# HitconBadge2018.net
KiCad netlist of a schematic drawn in EAGLE
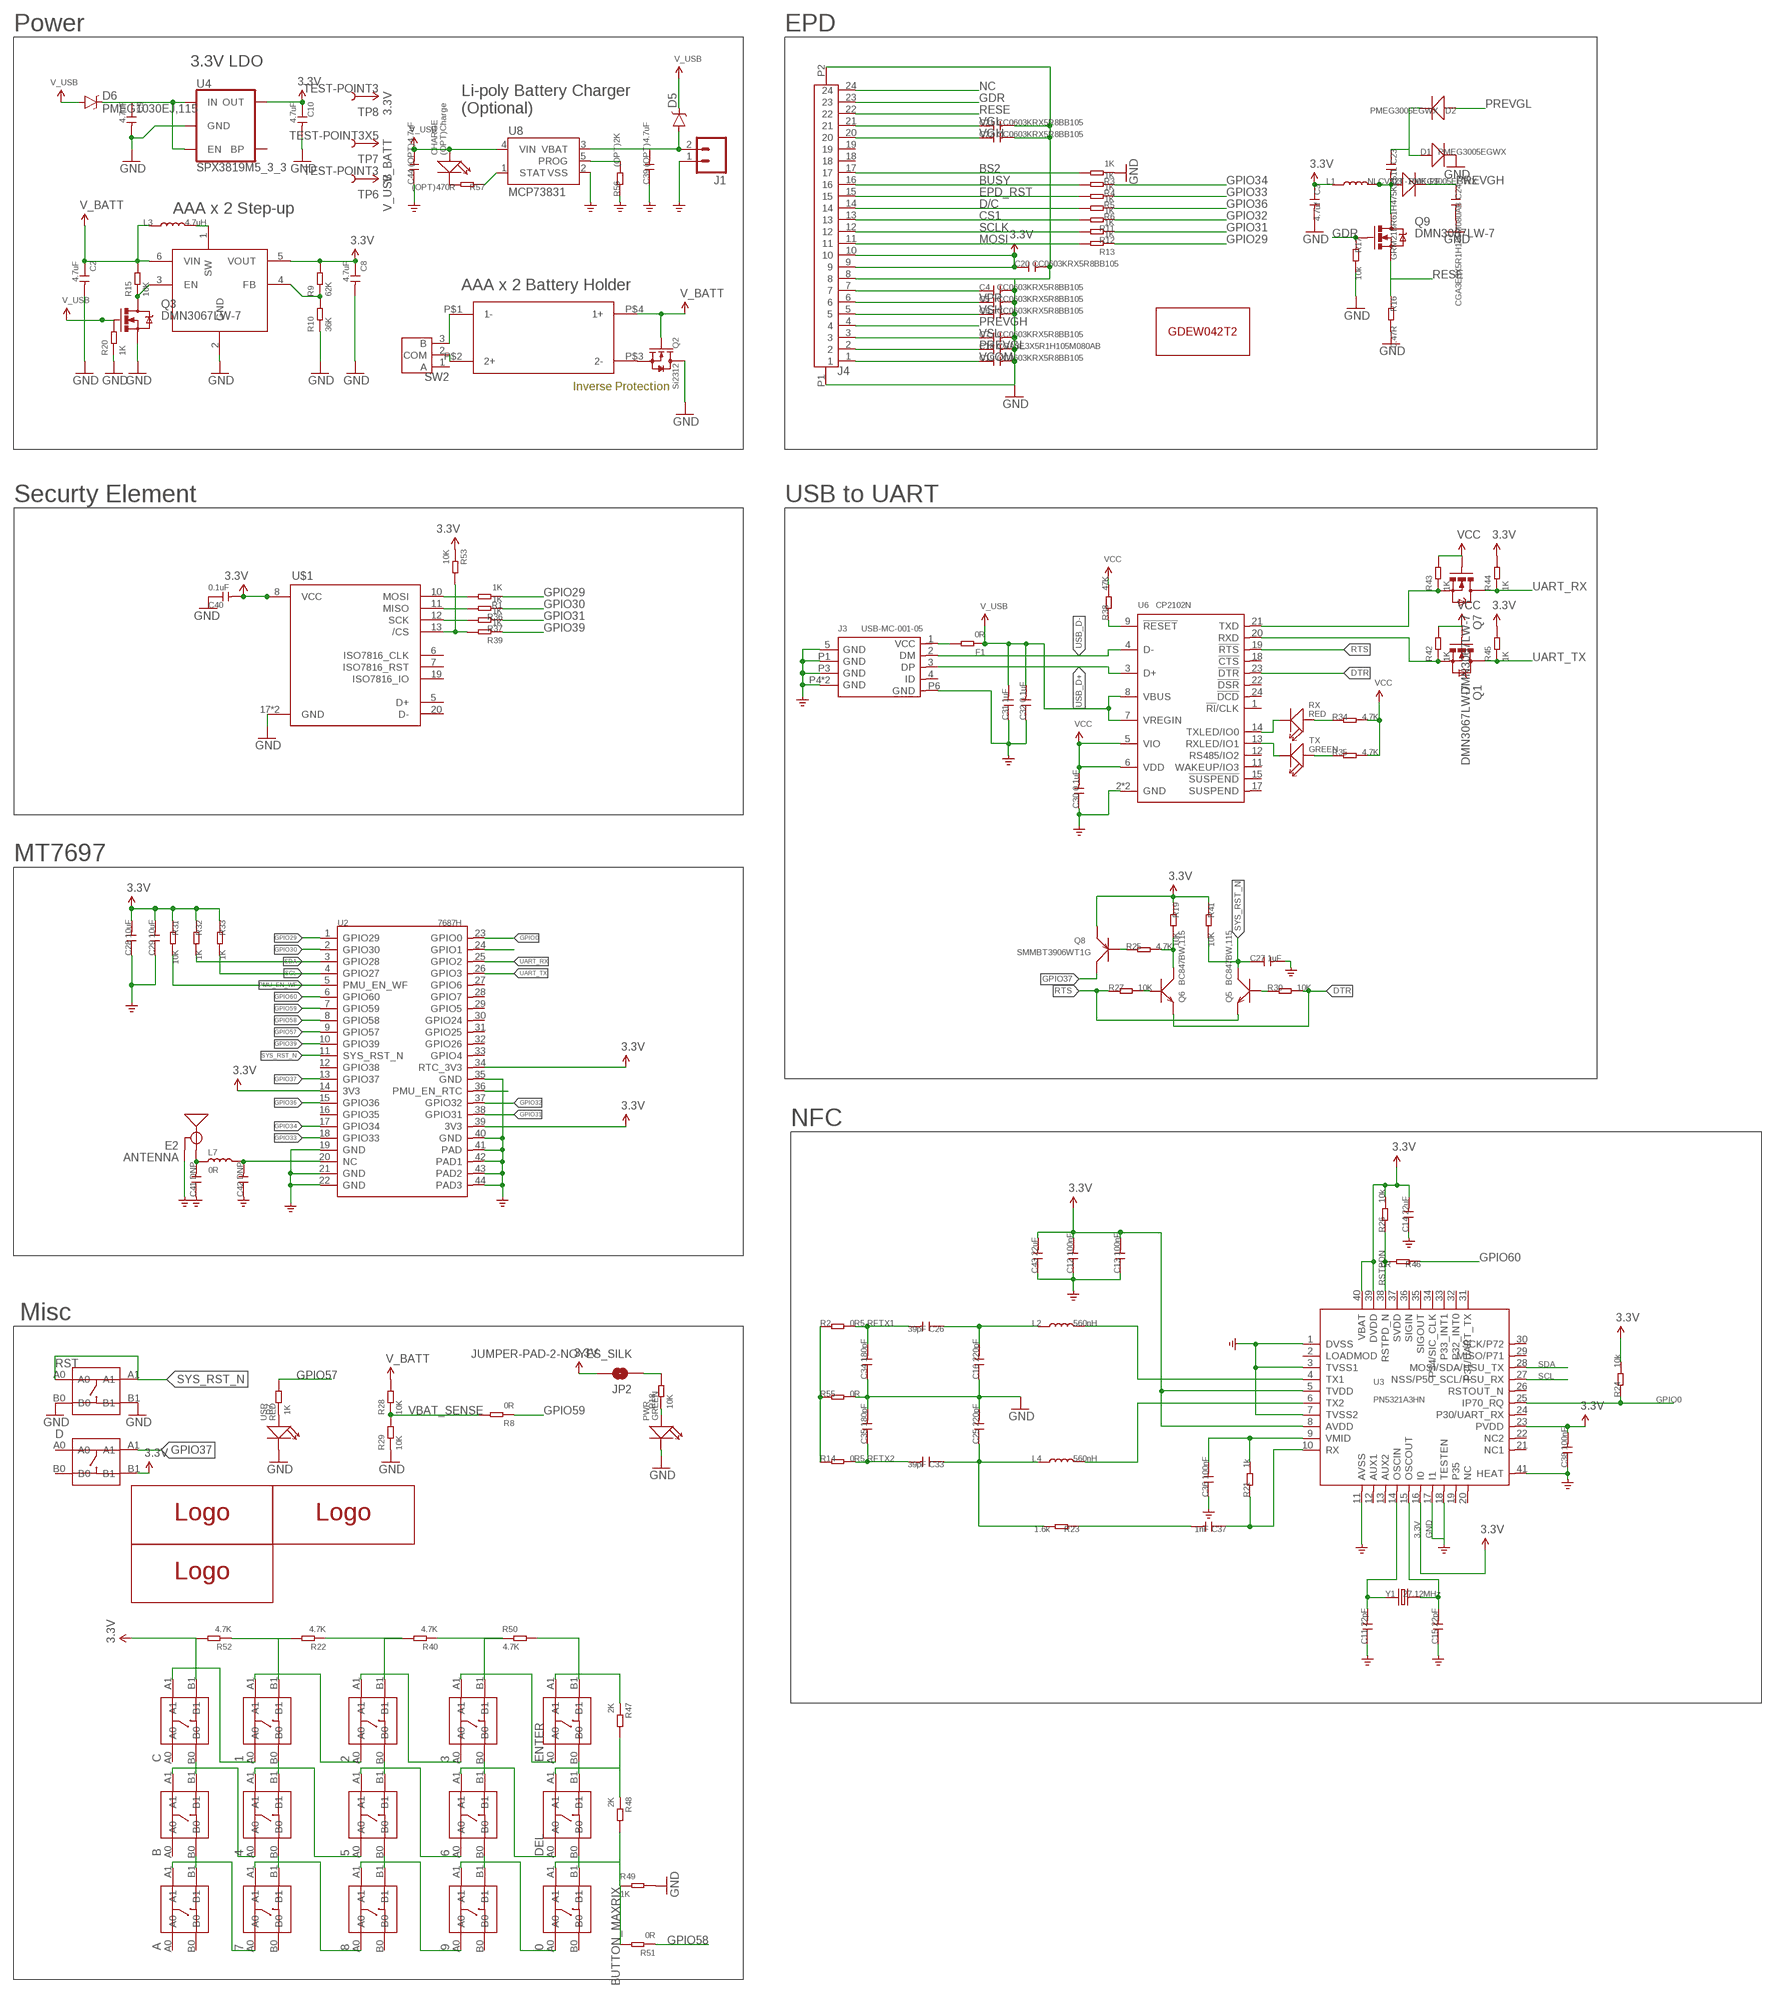
[diagram p0: schematic, sheet 1]

(export (version "E")
  (design (tool "Eeschema 10.0.6"))
  (components
    (comp (ref "0")
      (value "BUTTON-4P-3.3X3.3")
      (footprint "eagle-import:4P-SMD-3.4X3.4X1.3H")
      (libsource (lib "eagle-import") (part "BUTTON-4P-3.3X3.3"))
    )
    (comp (ref "1")
      (value "BUTTON-4P-3.3X3.3")
      (footprint "eagle-import:4P-SMD-3.4X3.4X1.3H")
      (libsource (lib "eagle-import") (part "BUTTON-4P-3.3X3.3"))
    )
    (comp (ref "2")
      (value "BUTTON-4P-3.3X3.3")
      (footprint "eagle-import:4P-SMD-3.4X3.4X1.3H")
      (libsource (lib "eagle-import") (part "BUTTON-4P-3.3X3.3"))
    )
    (comp (ref "3")
      (value "BUTTON-4P-3.3X3.3")
      (footprint "eagle-import:4P-SMD-3.4X3.4X1.3H")
      (libsource (lib "eagle-import") (part "BUTTON-4P-3.3X3.3"))
    )
    (comp (ref "4")
      (value "BUTTON-4P-3.3X3.3")
      (footprint "eagle-import:4P-SMD-3.4X3.4X1.3H")
      (libsource (lib "eagle-import") (part "BUTTON-4P-3.3X3.3"))
    )
    (comp (ref "5")
      (value "BUTTON-4P-3.3X3.3")
      (footprint "eagle-import:4P-SMD-3.4X3.4X1.3H")
      (libsource (lib "eagle-import") (part "BUTTON-4P-3.3X3.3"))
    )
    (comp (ref "6")
      (value "BUTTON-4P-3.3X3.3")
      (footprint "eagle-import:4P-SMD-3.4X3.4X1.3H")
      (libsource (lib "eagle-import") (part "BUTTON-4P-3.3X3.3"))
    )
    (comp (ref "7")
      (value "BUTTON-4P-3.3X3.3")
      (footprint "eagle-import:4P-SMD-3.4X3.4X1.3H")
      (libsource (lib "eagle-import") (part "BUTTON-4P-3.3X3.3"))
    )
    (comp (ref "8")
      (value "BUTTON-4P-3.3X3.3")
      (footprint "eagle-import:4P-SMD-3.4X3.4X1.3H")
      (libsource (lib "eagle-import") (part "BUTTON-4P-3.3X3.3"))
    )
    (comp (ref "9")
      (value "BUTTON-4P-3.3X3.3")
      (footprint "eagle-import:4P-SMD-3.4X3.4X1.3H")
      (libsource (lib "eagle-import") (part "BUTTON-4P-3.3X3.3"))
    )
    (comp (ref "A")
      (value "BUTTON-4P-3.3X3.3")
      (footprint "eagle-import:4P-SMD-3.4X3.4X1.3H")
      (libsource (lib "eagle-import") (part "BUTTON-4P-3.3X3.3"))
    )
    (comp (ref "B")
      (value "BUTTON-4P-3.3X3.3")
      (footprint "eagle-import:4P-SMD-3.4X3.4X1.3H")
      (libsource (lib "eagle-import") (part "BUTTON-4P-3.3X3.3"))
    )
    (comp (ref "C")
      (value "BUTTON-4P-3.3X3.3")
      (footprint "eagle-import:4P-SMD-3.4X3.4X1.3H")
      (libsource (lib "eagle-import") (part "BUTTON-4P-3.3X3.3"))
    )
    (comp (ref "C2")
      (value "4.7uF")
      (footprint "eagle-import:C0603@1")
      (libsource (lib "eagle-import") (part "CAP-0603"))
    )
    (comp (ref "C3")
      (value "4.7uf")
      (footprint "eagle-import:C0603")
      (libsource (lib "eagle-import") (part "C-0603"))
    )
    (comp (ref "C4")
      (value "CC0603KRX5R8BB105")
      (footprint "eagle-import:C0603")
      (libsource (lib "eagle-import") (part "C-0603"))
    )
    (comp (ref "C5")
      (value "CC0603KRX5R8BB105")
      (footprint "eagle-import:C0603")
      (libsource (lib "eagle-import") (part "C-0603"))
    )
    (comp (ref "C6")
      (value "CC0603KRX5R8BB105")
      (footprint "eagle-import:C0603")
      (libsource (lib "eagle-import") (part "C-0603"))
    )
    (comp (ref "C7")
      (value "CC0603KRX5R8BB105")
      (footprint "eagle-import:C0603")
      (libsource (lib "eagle-import") (part "C-0603"))
    )
    (comp (ref "C8")
      (value "4.7uF")
      (footprint "eagle-import:C0603@1")
      (libsource (lib "eagle-import") (part "CAP-0603"))
    )
    (comp (ref "C9")
      (value "4.7uF")
      (footprint "eagle-import:C0603@1")
      (libsource (lib "eagle-import") (part "CAP-0603"))
    )
    (comp (ref "C10")
      (value "4.7uF")
      (footprint "eagle-import:C0603@1")
      (libsource (lib "eagle-import") (part "CAP-0603"))
    )
    (comp (ref "C11")
      (value "22pF")
      (footprint "eagle-import:C0402")
      (libsource (lib "eagle-import") (part "C-0402"))
    )
    (comp (ref "C12")
      (value "100nF")
      (footprint "eagle-import:C0402")
      (libsource (lib "eagle-import") (part "C-0402"))
    )
    (comp (ref "C13")
      (value "100nF")
      (footprint "eagle-import:C0402")
      (libsource (lib "eagle-import") (part "C-0402"))
    )
    (comp (ref "C14")
      (value "22uF")
      (footprint "eagle-import:C0603")
      (libsource (lib "eagle-import") (part "C-0603"))
    )
    (comp (ref "C15")
      (value "22pF")
      (footprint "eagle-import:C0402")
      (libsource (lib "eagle-import") (part "C-0402"))
    )
    (comp (ref "C16")
      (value "220pF")
      (footprint "eagle-import:C0402")
      (libsource (lib "eagle-import") (part "C-0402"))
    )
    (comp (ref "C18")
      (value "CGA3E3X5R1H105M080AB")
      (footprint "eagle-import:C0603")
      (libsource (lib "eagle-import") (part "C-0603"))
    )
    (comp (ref "C19")
      (value "CC0603KRX5R8BB105")
      (footprint "eagle-import:C0603")
      (libsource (lib "eagle-import") (part "C-0603"))
    )
    (comp (ref "C20")
      (value "CC0603KRX5R8BB105")
      (footprint "eagle-import:C0603")
      (libsource (lib "eagle-import") (part "C-0603"))
    )
    (comp (ref "C21")
      (value "CC0603KRX5R8BB105")
      (footprint "eagle-import:C0603")
      (libsource (lib "eagle-import") (part "C-0603"))
    )
    (comp (ref "C22")
      (value "CC0603KRX5R8BB105")
      (footprint "eagle-import:C0603")
      (libsource (lib "eagle-import") (part "C-0603"))
    )
    (comp (ref "C23")
      (value "GRM21BR61H475KE51L")
      (footprint "eagle-import:C0805")
      (libsource (lib "eagle-import") (part "C-0805"))
    )
    (comp (ref "C24")
      (value "CGA3E3X5R1H105M080AB")
      (footprint "eagle-import:C0603")
      (libsource (lib "eagle-import") (part "C-0603"))
    )
    (comp (ref "C25")
      (value "220pF")
      (footprint "eagle-import:C0402")
      (libsource (lib "eagle-import") (part "C-0402"))
    )
    (comp (ref "C26")
      (value "39pF")
      (footprint "eagle-import:C0402")
      (libsource (lib "eagle-import") (part "C-0402"))
    )
    (comp (ref "C27")
      (value "1uF")
      (footprint "eagle-import:C0402")
      (libsource (lib "eagle-import") (part "C-0402"))
    )
    (comp (ref "C28")
      (value "10uF")
      (footprint "eagle-import:C0603")
      (libsource (lib "eagle-import") (part "C-0603"))
    )
    (comp (ref "C29")
      (value "10uF")
      (footprint "eagle-import:C0603")
      (libsource (lib "eagle-import") (part "C-0603"))
    )
    (comp (ref "C30")
      (value "0.1uF")
      (footprint "eagle-import:C0402")
      (libsource (lib "eagle-import") (part "C-0402"))
    )
    (comp (ref "C31")
      (value "1uF")
      (footprint "eagle-import:C0402")
      (libsource (lib "eagle-import") (part "C-0402"))
    )
    (comp (ref "C32")
      (value "0.1uF")
      (footprint "eagle-import:C0402")
      (libsource (lib "eagle-import") (part "C-0402"))
    )
    (comp (ref "C33")
      (value "39pF")
      (footprint "eagle-import:C0402")
      (libsource (lib "eagle-import") (part "C-0402"))
    )
    (comp (ref "C34")
      (value "180pF")
      (footprint "eagle-import:C0402")
      (libsource (lib "eagle-import") (part "C-0402"))
    )
    (comp (ref "C35")
      (value "180pF")
      (footprint "eagle-import:C0402")
      (libsource (lib "eagle-import") (part "C-0402"))
    )
    (comp (ref "C36")
      (value "100nF")
      (footprint "eagle-import:C0402")
      (libsource (lib "eagle-import") (part "C-0402"))
    )
    (comp (ref "C37")
      (value "1nF")
      (footprint "eagle-import:C0402")
      (libsource (lib "eagle-import") (part "C-0402"))
    )
    (comp (ref "C38")
      (value "100nF")
      (footprint "eagle-import:C0402")
      (libsource (lib "eagle-import") (part "C-0402"))
    )
    (comp (ref "C39")
      (value "(OPT)4.7uF")
      (footprint "eagle-import:C0603")
      (libsource (lib "eagle-import") (part "C-0603"))
    )
    (comp (ref "C40")
      (value "0.1uF")
      (footprint "eagle-import:C0402@1")
      (libsource (lib "eagle-import") (part "CAP-0402"))
    )
    (comp (ref "C41")
      (value "DNP")
      (footprint "eagle-import:C0402")
      (libsource (lib "eagle-import") (part "C-0402"))
    )
    (comp (ref "C42")
      (value "DNP")
      (footprint "eagle-import:C0402")
      (libsource (lib "eagle-import") (part "C-0402"))
    )
    (comp (ref "C43")
      (value "22uF")
      (footprint "eagle-import:C0603")
      (libsource (lib "eagle-import") (part "C-0603"))
    )
    (comp (ref "C44")
      (value "(OPT)4.7uF")
      (footprint "eagle-import:C0603")
      (libsource (lib "eagle-import") (part "C-0603"))
    )
    (comp (ref "CHARGE")
      (value "(OPT)Charge")
      (footprint "eagle-import:LED-0603")
      (libsource (lib "eagle-import") (part "LED'0603'"))
    )
    (comp (ref "D")
      (value "BUTTON-4P-3.3X3.3")
      (footprint "eagle-import:4P-SMD-3.4X3.4X1.3H")
      (libsource (lib "eagle-import") (part "BUTTON-4P-3.3X3.3"))
    )
    (comp (ref "D1")
      (value "PMEG3005EGWX")
      (footprint "eagle-import:SOD123")
      (libsource (lib "eagle-import") (part "D'1206'"))
    )
    (comp (ref "D2")
      (value "PMEG3005EGWX")
      (footprint "eagle-import:SOD123")
      (libsource (lib "eagle-import") (part "D'1206'"))
    )
    (comp (ref "D3")
      (value "PMEG3005EGWX")
      (footprint "eagle-import:SOD123")
      (libsource (lib "eagle-import") (part "D'1206'"))
    )
    (comp (ref "D5")
      (value "(OPT)PMEG1030EJ,115")
      (footprint "eagle-import:SOD-323")
      (libsource (lib "eagle-import") (part "DIODE-SCHOTTKY-BAT20J"))
    )
    (comp (ref "D6")
      (value "PMEG1030EJ,115")
      (footprint "eagle-import:SOD-323")
      (libsource (lib "eagle-import") (part "DIODE-SCHOTTKY-BAT20J"))
    )
    (comp (ref "DEL")
      (value "BUTTON-4P-3.3X3.3")
      (footprint "eagle-import:4P-SMD-3.4X3.4X1.3H")
      (libsource (lib "eagle-import") (part "BUTTON-4P-3.3X3.3"))
    )
    (comp (ref "E2")
      (value "ANTENNA")
      (footprint "eagle-import:2450AT18D0100E")
      (libsource (lib "eagle-import") (part "ANTENNA"))
    )
    (comp (ref "ENTER")
      (value "BUTTON-4P-3.3X3.3")
      (footprint "eagle-import:4P-SMD-3.4X3.4X1.3H")
      (libsource (lib "eagle-import") (part "BUTTON-4P-3.3X3.3"))
    )
    (comp (ref "F1")
      (value "0R")
      (footprint "eagle-import:R0603")
      (libsource (lib "eagle-import") (part "RES-0603"))
    )
    (comp (ref "J1")
      (value "M02-JST-2MM-SMT")
      (footprint "eagle-import:JST-2-SMD")
      (libsource (lib "eagle-import") (part "M02-JST-2MM-SMT"))
    )
    (comp (ref "J3")
      (value "USB-MC-001-05")
      (footprint "eagle-import:MICRO-USB5+5P-SMD-0.65-7.2X5.06MM")
      (libsource (lib "eagle-import") (part "MICRO-USB5+4P"))
    )
    (comp (ref "J4")
      (value "FPC-CONNECTOR-24P-0.5'ST-FPC-052024-B'")
      (footprint "eagle-import:24P-0.5")
      (libsource (lib "eagle-import") (part "FPC-CONNECTOR-24P-0.5'ST-FPC-052024-B'"))
    )
    (comp (ref "JP2")
      (value "JUMPER-PAD-2-NOYES_SILK")
      (footprint "eagle-import:PAD-JUMPER-2-NO_YES_SILK")
      (libsource (lib "eagle-import") (part "JUMPER-PAD-2-NOYES_SILK"))
    )
    (comp (ref "L1")
      (value "NLCV32T-100K-PF")
      (footprint "eagle-import:1813@1")
      (libsource (lib "eagle-import") (part "L'1813'"))
    )
    (comp (ref "L2")
      (value "560nH")
      (footprint "eagle-import:L0603@1")
      (libsource (lib "eagle-import") (part "L'0603'"))
    )
    (comp (ref "L3")
      (value "4.7uH")
      (footprint "eagle-import:1616BZ@1")
      (libsource (lib "eagle-import") (part "L'1616BZ'"))
    )
    (comp (ref "L4")
      (value "560nH")
      (footprint "eagle-import:L0603@1")
      (libsource (lib "eagle-import") (part "L'0603'"))
    )
    (comp (ref "L7")
      (value "0R")
      (footprint "eagle-import:L0402")
      (libsource (lib "eagle-import") (part "INDUCTOR/FERRITE-BEAD-0402"))
    )
    (comp (ref "PWR")
      (value "GREEN")
      (footprint "eagle-import:LED-0603")
      (libsource (lib "eagle-import") (part "LED'0603'"))
    )
    (comp (ref "Q1")
      (value "DMN3067LW-7")
      (footprint "eagle-import:SOT323")
      (libsource (lib "eagle-import") (part "MOSFET-NCHANNEL2N7002PW"))
    )
    (comp (ref "Q2")
      (value "Si2312")
      (footprint "eagle-import:SOT23")
      (libsource (lib "eagle-import") (part "MOSFET-N'SOT23'"))
    )
    (comp (ref "Q3")
      (value "DMN3067LW-7")
      (footprint "eagle-import:SOT323")
      (libsource (lib "eagle-import") (part "MOSFET-NCHANNEL2N7002PW"))
    )
    (comp (ref "Q5")
      (value "BC847BW,115")
      (footprint "eagle-import:SOT-323")
      (libsource (lib "eagle-import") (part "TRANSISTOR-NPN-SOT323"))
    )
    (comp (ref "Q6")
      (value "BC847BW,115")
      (footprint "eagle-import:SOT-323")
      (libsource (lib "eagle-import") (part "TRANSISTOR-NPN-SOT323"))
    )
    (comp (ref "Q7")
      (value "DMN3067LW-7")
      (footprint "eagle-import:SOT323")
      (libsource (lib "eagle-import") (part "MOSFET-NCHANNEL2N7002PW"))
    )
    (comp (ref "Q8")
      (value "SMMBT3906WT1G")
      (footprint "eagle-import:SOT-323")
      (libsource (lib "eagle-import") (part "TRANSISTOR-PNP"))
    )
    (comp (ref "Q9")
      (value "DMN3067LW-7")
      (footprint "eagle-import:SOT323")
      (libsource (lib "eagle-import") (part "MOSFET-NCHANNEL2N7002PW"))
    )
    (comp (ref "R1")
      (value "1K")
      (footprint "eagle-import:R0402")
      (libsource (lib "eagle-import") (part "RES-0402"))
    )
    (comp (ref "R2")
      (value "0R5")
      (footprint "eagle-import:R0402")
      (libsource (lib "eagle-import") (part "R-0402"))
    )
    (comp (ref "R3")
      (value "1K")
      (footprint "eagle-import:R0402")
      (libsource (lib "eagle-import") (part "RES-0402"))
    )
    (comp (ref "R4")
      (value "1K")
      (footprint "eagle-import:R0402")
      (libsource (lib "eagle-import") (part "RES-0402"))
    )
    (comp (ref "R5")
      (value "1K")
      (footprint "eagle-import:R0402")
      (libsource (lib "eagle-import") (part "RES-0402"))
    )
    (comp (ref "R6")
      (value "1K")
      (footprint "eagle-import:R0402")
      (libsource (lib "eagle-import") (part "RES-0402"))
    )
    (comp (ref "R7")
      (value "1K")
      (footprint "eagle-import:R0402")
      (libsource (lib "eagle-import") (part "RES-0402"))
    )
    (comp (ref "R8")
      (value "0R")
      (footprint "eagle-import:R0402")
      (libsource (lib "eagle-import") (part "RES-0402"))
    )
    (comp (ref "R9")
      (value "62K")
      (footprint "eagle-import:R0402")
      (libsource (lib "eagle-import") (part "RES-0402"))
    )
    (comp (ref "R10")
      (value "36K")
      (footprint "eagle-import:R0402")
      (libsource (lib "eagle-import") (part "RES-0402"))
    )
    (comp (ref "R11")
      (value "1K")
      (footprint "eagle-import:R0402")
      (libsource (lib "eagle-import") (part "RES-0402"))
    )
    (comp (ref "R12")
      (value "1K")
      (footprint "eagle-import:R0402")
      (libsource (lib "eagle-import") (part "RES-0402"))
    )
    (comp (ref "R13")
      (value "1K")
      (footprint "eagle-import:R0402")
      (libsource (lib "eagle-import") (part "RES-0402"))
    )
    (comp (ref "R14")
      (value "0R5")
      (footprint "eagle-import:R0402")
      (libsource (lib "eagle-import") (part "R-0402"))
    )
    (comp (ref "R15")
      (value "10K")
      (footprint "eagle-import:R0402")
      (libsource (lib "eagle-import") (part "RES-0402"))
    )
    (comp (ref "R16")
      (value "0.47R")
      (footprint "eagle-import:R0402")
      (libsource (lib "eagle-import") (part "R-0402"))
    )
    (comp (ref "R17")
      (value "10k")
      (footprint "eagle-import:R0402")
      (libsource (lib "eagle-import") (part "R-0402"))
    )
    (comp (ref "R18")
      (value "10K")
      (footprint "eagle-import:R0402")
      (libsource (lib "eagle-import") (part "RES-0402"))
    )
    (comp (ref "R19")
      (value "10K")
      (footprint "eagle-import:R0402")
      (libsource (lib "eagle-import") (part "R-0402"))
    )
    (comp (ref "R20")
      (value "1K")
      (footprint "eagle-import:R0402")
      (libsource (lib "eagle-import") (part "RES-0402"))
    )
    (comp (ref "R21")
      (value "1k")
      (footprint "eagle-import:R0402")
      (libsource (lib "eagle-import") (part "R-0402"))
    )
    (comp (ref "R22")
      (value "4.7K")
      (footprint "eagle-import:R0402")
      (libsource (lib "eagle-import") (part "RES-0402"))
    )
    (comp (ref "R23")
      (value "1.6k")
      (footprint "eagle-import:R0402")
      (libsource (lib "eagle-import") (part "R-0402"))
    )
    (comp (ref "R24")
      (value "10k")
      (footprint "eagle-import:R0402")
      (libsource (lib "eagle-import") (part "R-0402"))
    )
    (comp (ref "R25")
      (value "4.7K")
      (footprint "eagle-import:R0402")
      (libsource (lib "eagle-import") (part "R-0402"))
    )
    (comp (ref "R26")
      (value "10k")
      (footprint "eagle-import:R0402")
      (libsource (lib "eagle-import") (part "R-0402"))
    )
    (comp (ref "R27")
      (value "10K")
      (footprint "eagle-import:R0402")
      (libsource (lib "eagle-import") (part "R-0402"))
    )
    (comp (ref "R28")
      (value "10K")
      (footprint "eagle-import:R0402")
      (libsource (lib "eagle-import") (part "RES-0402"))
    )
    (comp (ref "R29")
      (value "10K")
      (footprint "eagle-import:R0402")
      (libsource (lib "eagle-import") (part "RES-0402"))
    )
    (comp (ref "R30")
      (value "10K")
      (footprint "eagle-import:R0402")
      (libsource (lib "eagle-import") (part "R-0402"))
    )
    (comp (ref "R31")
      (value "10K")
      (footprint "eagle-import:R0402")
      (libsource (lib "eagle-import") (part "R-0402"))
    )
    (comp (ref "R32")
      (value "1K")
      (footprint "eagle-import:R0402")
      (libsource (lib "eagle-import") (part "R-0402"))
    )
    (comp (ref "R33")
      (value "1K")
      (footprint "eagle-import:R0402")
      (libsource (lib "eagle-import") (part "R-0402"))
    )
    (comp (ref "R34")
      (value "4.7K")
      (footprint "eagle-import:R0402")
      (libsource (lib "eagle-import") (part "R-0402"))
    )
    (comp (ref "R35")
      (value "4.7K")
      (footprint "eagle-import:R0402")
      (libsource (lib "eagle-import") (part "R-0402"))
    )
    (comp (ref "R36")
      (value "1K")
      (footprint "eagle-import:R0402")
      (libsource (lib "eagle-import") (part "RES-0402"))
    )
    (comp (ref "R37")
      (value "1K")
      (footprint "eagle-import:R0402")
      (libsource (lib "eagle-import") (part "RES-0402"))
    )
    (comp (ref "R38")
      (value "47K")
      (footprint "eagle-import:R0402")
      (libsource (lib "eagle-import") (part "R-0402"))
    )
    (comp (ref "R39")
      (value "1K")
      (footprint "eagle-import:R0402")
      (libsource (lib "eagle-import") (part "RES-0402"))
    )
    (comp (ref "R40")
      (value "4.7K")
      (footprint "eagle-import:R0402")
      (libsource (lib "eagle-import") (part "RES-0402"))
    )
    (comp (ref "R41")
      (value "10K")
      (footprint "eagle-import:R0402")
      (libsource (lib "eagle-import") (part "R-0402"))
    )
    (comp (ref "R42")
      (value "1K")
      (footprint "eagle-import:R0402")
      (libsource (lib "eagle-import") (part "RES-0402"))
    )
    (comp (ref "R43")
      (value "1K")
      (footprint "eagle-import:R0402")
      (libsource (lib "eagle-import") (part "RES-0402"))
    )
    (comp (ref "R44")
      (value "1K")
      (footprint "eagle-import:R0402")
      (libsource (lib "eagle-import") (part "RES-0402"))
    )
    (comp (ref "R45")
      (value "1K")
      (footprint "eagle-import:R0402")
      (libsource (lib "eagle-import") (part "RES-0402"))
    )
    (comp (ref "R46")
      (value "0R")
      (footprint "eagle-import:R0402")
      (libsource (lib "eagle-import") (part "R-0402"))
    )
    (comp (ref "R47")
      (value "2K")
      (footprint "eagle-import:R0402")
      (libsource (lib "eagle-import") (part "RES-0402"))
    )
    (comp (ref "R48")
      (value "2K")
      (footprint "eagle-import:R0402")
      (libsource (lib "eagle-import") (part "RES-0402"))
    )
    (comp (ref "R49")
      (value "1K")
      (footprint "eagle-import:R0402")
      (libsource (lib "eagle-import") (part "RES-0402"))
    )
    (comp (ref "R50")
      (value "4.7K")
      (footprint "eagle-import:R0402")
      (libsource (lib "eagle-import") (part "RES-0402"))
    )
    (comp (ref "R51")
      (value "0R")
      (footprint "eagle-import:R0402")
      (libsource (lib "eagle-import") (part "RES-0402"))
    )
    (comp (ref "R52")
      (value "4.7K")
      (footprint "eagle-import:R0402")
      (libsource (lib "eagle-import") (part "RES-0402"))
    )
    (comp (ref "R53")
      (value "10K")
      (footprint "eagle-import:R0402")
      (libsource (lib "eagle-import") (part "RES-0402"))
    )
    (comp (ref "R55")
      (value "0R")
      (footprint "eagle-import:R0402")
      (libsource (lib "eagle-import") (part "R-0402"))
    )
    (comp (ref "R56")
      (value "(OPT)2K")
      (footprint "eagle-import:R0402")
      (libsource (lib "eagle-import") (part "R-0402"))
    )
    (comp (ref "R57")
      (value "(OPT)470R")
      (footprint "eagle-import:R0402")
      (libsource (lib "eagle-import") (part "R-0402"))
    )
    (comp (ref "RST")
      (value "BUTTON-4P-3.3X3.3")
      (footprint "eagle-import:4P-SMD-3.4X3.4X1.3H")
      (libsource (lib "eagle-import") (part "BUTTON-4P-3.3X3.3"))
    )
    (comp (ref "RX")
      (value "RED")
      (footprint "eagle-import:LED-0603")
      (libsource (lib "eagle-import") (part "LED'0603'"))
    )
    (comp (ref "SW2")
      (value "SWITCH-2H-3P'--'")
      (footprint "eagle-import:3P-2CH-3.54X8.5")
      (libsource (lib "eagle-import") (part "SWITCH-2H-3P'--'"))
    )
    (comp (ref "TP6")
      (value "TEST-POINT3")
      (footprint "eagle-import:PAD.03X.03")
      (libsource (lib "eagle-import") (part "TEST-POINT3"))
    )
    (comp (ref "TP7")
      (value "TEST-POINT3X5")
      (footprint "eagle-import:PAD.03X.05")
      (libsource (lib "eagle-import") (part "TEST-POINT3X5"))
    )
    (comp (ref "TP8")
      (value "TEST-POINT3")
      (footprint "eagle-import:PAD.03X.03")
      (libsource (lib "eagle-import") (part "TEST-POINT3"))
    )
    (comp (ref "TX")
      (value "GREEN")
      (footprint "eagle-import:LED-0603")
      (libsource (lib "eagle-import") (part "LED'0603'"))
    )
    (comp (ref "U$1")
      (value "SLE97")
      (footprint "eagle-import:QFN-32")
      (libsource (lib "eagle-import") (part "SLE97"))
    )
    (comp (ref "U$2")
      (value "HITCON_LOGOHITCON")
      (footprint "eagle-import:HITCON_LOGO")
      (libsource (lib "eagle-import") (part "HITCON_LOGOHITCON"))
    )
    (comp (ref "U$3")
      (value "HITCON_LOGOMEDIATEK")
      (footprint "eagle-import:MEDIATEK")
      (libsource (lib "eagle-import") (part "HITCON_LOGOMEDIATEK"))
    )
    (comp (ref "U$4")
      (value "AAAX2")
      (footprint "eagle-import:AAAX2")
      (libsource (lib "eagle-import") (part "AAAX2"))
    )
    (comp (ref "U$5")
      (value "213")
      (footprint "eagle-import:213")
      (libsource (lib "eagle-import") (part "213"))
    )
    (comp (ref "U$6")
      (value "HITCON_LOGOIKV")
      (footprint "eagle-import:IKV")
      (libsource (lib "eagle-import") (part "HITCON_LOGOIKV"))
    )
    (comp (ref "U1")
      (value "MCP1640")
      (footprint "eagle-import:SOT23-6")
      (libsource (lib "eagle-import") (part "MCP1640"))
    )
    (comp (ref "U2")
      (value "7687H")
      (footprint "eagle-import:MODULE44P-1.6-18X18X1.3MM")
      (libsource (lib "eagle-import") (part "MODULE-SIP-AI7697H"))
    )
    (comp (ref "U3")
      (value "PN5321A3HN")
      (footprint "eagle-import:HVQFN40")
      (libsource (lib "eagle-import") (part "PN532-HVQFN40"))
    )
    (comp (ref "U4")
      (value "SPX3819M5_3_3")
      (footprint "eagle-import:SOT23-5")
      (libsource (lib "eagle-import") (part "V_REG_SPX3819-SOT23-5"))
    )
    (comp (ref "U6")
      (value "CP2102N")
      (footprint "eagle-import:QFN24G-0.5-4X4MM")
      (libsource (lib "eagle-import") (part "CONVERTER-CP2102N(QFN24)"))
    )
    (comp (ref "U8")
      (value "MCP73831")
      (footprint "eagle-import:SOT23-5")
      (libsource (lib "eagle-import") (part "MCP73831"))
    )
    (comp (ref "USR")
      (value "RED")
      (footprint "eagle-import:LED-0603")
      (libsource (lib "eagle-import") (part "LED'0603'"))
    )
    (comp (ref "Y1")
      (value "27.12MHz")
      (footprint "eagle-import:4P-SMD-3.2X2.5")
      (libsource (lib "eagle-import") (part "CRYSTAL'3225'"))
    )
  )
  (nets
    (net (code "1") (name "/BS2") (class "Default")
      (node (ref "J4") (pin "17") (pinfunction "17_17") (pintype "bidirectional"))
      (node (ref "R3") (pin "2") (pinfunction "2_2") (pintype "passive"))
    )
    (net (code "2") (name "/BUSY") (class "Default")
      (node (ref "J4") (pin "16") (pinfunction "16_16") (pintype "bidirectional"))
      (node (ref "R4") (pin "2") (pinfunction "2_2") (pintype "passive"))
    )
    (net (code "3") (name "/BUTTON_MAXRIX") (class "Default")
      (node (ref "0") (pin "A1") (pinfunction "A1_A1") (pintype "bidirectional"))
      (node (ref "R48") (pin "2") (pinfunction "2_2") (pintype "passive"))
      (node (ref "R49") (pin "1") (pinfunction "1_1") (pintype "passive"))
      (node (ref "R51") (pin "2") (pinfunction "2_2") (pintype "passive"))
    )
    (net (code "4") (name "/CS1") (class "Default")
      (node (ref "J4") (pin "13") (pinfunction "13_13") (pintype "bidirectional"))
      (node (ref "R11") (pin "2") (pinfunction "2_2") (pintype "passive"))
    )
    (net (code "5") (name "/D{slash}C") (class "Default")
      (node (ref "J4") (pin "14") (pinfunction "14_14") (pintype "bidirectional"))
      (node (ref "R6") (pin "2") (pinfunction "2_2") (pintype "passive"))
    )
    (net (code "6") (name "/EPD_RST") (class "Default")
      (node (ref "J4") (pin "15") (pinfunction "15_15") (pintype "bidirectional"))
      (node (ref "R5") (pin "2") (pinfunction "2_2") (pintype "passive"))
    )
    (net (code "7") (name "/GDR") (class "Default")
      (node (ref "J4") (pin "23") (pinfunction "23_23") (pintype "bidirectional"))
      (node (ref "Q9") (pin "1") (pinfunction "G_1") (pintype "passive"))
      (node (ref "R17") (pin "1") (pinfunction "1_1") (pintype "passive"))
    )
    (net (code "8") (name "/MOSI") (class "Default")
      (node (ref "J4") (pin "11") (pinfunction "11_11") (pintype "bidirectional"))
      (node (ref "R13") (pin "2") (pinfunction "2_2") (pintype "passive"))
    )
    (net (code "9") (name "/NC") (class "Default")
      (node (ref "J4") (pin "24") (pinfunction "24_24") (pintype "bidirectional"))
    )
    (net (code "10") (name "/PREVGH") (class "Default")
      (node (ref "C24") (pin "1") (pinfunction "1_1") (pintype "passive"))
      (node (ref "D3") (pin "-") (pinfunction "-_-") (pintype "passive"))
      (node (ref "J4") (pin "4") (pinfunction "4_4") (pintype "bidirectional"))
    )
    (net (code "11") (name "/PREVGL") (class "Default")
      (node (ref "C18") (pin "1") (pinfunction "1_1") (pintype "passive"))
      (node (ref "D2") (pin "+") (pinfunction "+_+") (pintype "passive"))
      (node (ref "J4") (pin "2") (pinfunction "2_2") (pintype "bidirectional"))
    )
    (net (code "12") (name "/RESE") (class "Default")
      (node (ref "J4") (pin "22") (pinfunction "22_22") (pintype "bidirectional"))
      (node (ref "Q9") (pin "2") (pinfunction "S_2") (pintype "passive"))
      (node (ref "R16") (pin "1") (pinfunction "1_1") (pintype "passive"))
    )
    (net (code "13") (name "/RFTX1") (class "Default")
      (node (ref "C26") (pin "2") (pinfunction "2_2") (pintype "passive"))
      (node (ref "C34") (pin "2") (pinfunction "2_2") (pintype "passive"))
      (node (ref "R2") (pin "2") (pinfunction "2_2") (pintype "passive"))
    )
    (net (code "14") (name "/RFTX2") (class "Default")
      (node (ref "C33") (pin "2") (pinfunction "2_2") (pintype "passive"))
      (node (ref "C35") (pin "1") (pinfunction "1_1") (pintype "passive"))
      (node (ref "R14") (pin "2") (pinfunction "2_2") (pintype "passive"))
    )
    (net (code "15") (name "/RSTPDN") (class "Default")
      (node (ref "R26") (pin "1") (pinfunction "1_1") (pintype "passive"))
      (node (ref "R46") (pin "2") (pinfunction "2_2") (pintype "passive"))
      (node (ref "U3") (pin "38") (pinfunction "RSTPD_N_38") (pintype "input"))
    )
    (net (code "16") (name "/SCLK") (class "Default")
      (node (ref "J4") (pin "12") (pinfunction "12_12") (pintype "bidirectional"))
      (node (ref "R12") (pin "2") (pinfunction "2_2") (pintype "passive"))
    )
    (net (code "17") (name "/SVDD") (class "Default")
      (node (ref "U3") (pin "37") (pinfunction "SVDD_37") (pintype "power_in"))
    )
    (net (code "18") (name "/VBAT_SENSE") (class "Default")
      (node (ref "R28") (pin "1") (pinfunction "1_1") (pintype "passive"))
      (node (ref "R29") (pin "2") (pinfunction "2_2") (pintype "passive"))
      (node (ref "R8") (pin "2") (pinfunction "2_2") (pintype "passive"))
    )
    (net (code "19") (name "/VCOM") (class "Default")
      (node (ref "C19") (pin "1") (pinfunction "1_1") (pintype "passive"))
      (node (ref "J4") (pin "1") (pinfunction "1_1") (pintype "bidirectional"))
    )
    (net (code "20") (name "/VGH") (class "Default")
      (node (ref "C22") (pin "1") (pinfunction "1_1") (pintype "passive"))
      (node (ref "J4") (pin "20") (pinfunction "20_20") (pintype "bidirectional"))
    )
    (net (code "21") (name "/VGL") (class "Default")
      (node (ref "C21") (pin "1") (pinfunction "1_1") (pintype "passive"))
      (node (ref "J4") (pin "21") (pinfunction "21_21") (pintype "bidirectional"))
    )
    (net (code "22") (name "/VPP") (class "Default")
      (node (ref "C5") (pin "1") (pinfunction "1_1") (pintype "passive"))
      (node (ref "J4") (pin "6") (pinfunction "6_6") (pintype "bidirectional"))
    )
    (net (code "23") (name "/VSH") (class "Default")
      (node (ref "C6") (pin "1") (pinfunction "1_1") (pintype "passive"))
      (node (ref "J4") (pin "5") (pinfunction "5_5") (pintype "bidirectional"))
    )
    (net (code "24") (name "/VSL") (class "Default")
      (node (ref "C7") (pin "1") (pinfunction "1_1") (pintype "passive"))
      (node (ref "J4") (pin "3") (pinfunction "3_3") (pintype "bidirectional"))
    )
    (net (code "25") (name "3.3V") (class "Default")
      (node (ref "C") (pin "B1") (pinfunction "B1_B1") (pintype "bidirectional"))
      (node (ref "C10") (pin "1") (pinfunction "1_1") (pintype "passive"))
      (node (ref "C12") (pin "2") (pinfunction "2_2") (pintype "passive"))
      (node (ref "C13") (pin "2") (pinfunction "2_2") (pintype "passive"))
      (node (ref "C14") (pin "2") (pinfunction "2_2") (pintype "passive"))
      (node (ref "C20") (pin "1") (pinfunction "1_1") (pintype "passive"))
      (node (ref "C28") (pin "2") (pinfunction "2_2") (pintype "passive"))
      (node (ref "C29") (pin "2") (pinfunction "2_2") (pintype "passive"))
      (node (ref "C3") (pin "1") (pinfunction "1_1") (pintype "passive"))
      (node (ref "C38") (pin "2") (pinfunction "2_2") (pintype "passive"))
      (node (ref "C40") (pin "2") (pinfunction "2_2") (pintype "passive"))
      (node (ref "C43") (pin "2") (pinfunction "2_2") (pintype "passive"))
      (node (ref "C8") (pin "1") (pinfunction "1_1") (pintype "passive"))
      (node (ref "D") (pin "B1") (pinfunction "B1_B1") (pintype "bidirectional"))
      (node (ref "J4") (pin "10") (pinfunction "10_10") (pintype "bidirectional"))
      (node (ref "J4") (pin "9") (pinfunction "9_9") (pintype "bidirectional"))
      (node (ref "JP2") (pin "2") (pinfunction "2_2") (pintype "passive"))
      (node (ref "L1") (pin "1") (pinfunction "1_1") (pintype "passive"))
      (node (ref "Q8") (pin "2") (pinfunction "E_2") (pintype "passive"))
      (node (ref "R19") (pin "1") (pinfunction "1_1") (pintype "passive"))
      (node (ref "R24") (pin "2") (pinfunction "2_2") (pintype "passive"))
      (node (ref "R26") (pin "2") (pinfunction "2_2") (pintype "passive"))
      (node (ref "R31") (pin "1") (pinfunction "1_1") (pintype "passive"))
      (node (ref "R32") (pin "1") (pinfunction "1_1") (pintype "passive"))
      (node (ref "R33") (pin "1") (pinfunction "1_1") (pintype "passive"))
      (node (ref "R41") (pin "1") (pinfunction "1_1") (pintype "passive"))
      (node (ref "R44") (pin "2") (pinfunction "2_2") (pintype "passive"))
      (node (ref "R45") (pin "2") (pinfunction "2_2") (pintype "passive"))
      (node (ref "R52") (pin "2") (pinfunction "2_2") (pintype "passive"))
      (node (ref "R53") (pin "1") (pinfunction "1_1") (pintype "passive"))
      (node (ref "R9") (pin "2") (pinfunction "2_2") (pintype "passive"))
      (node (ref "TP8") (pin "P$1") (pinfunction "1_P$1") (pintype "bidirectional"))
      (node (ref "U$1") (pin "8") (pinfunction "VCC_8") (pintype "bidirectional"))
      (node (ref "U1") (pin "5") (pinfunction "VOUT_5") (pintype "bidirectional"))
      (node (ref "U2") (pin "14") (pinfunction "3V3_14") (pintype "bidirectional"))
      (node (ref "U2") (pin "34") (pinfunction "RTC_3V3_34") (pintype "bidirectional"))
      (node (ref "U2") (pin "39") (pinfunction "3V3_39") (pintype "bidirectional"))
      (node (ref "U3") (pin "16") (pinfunction "I0_16") (pintype "input"))
      (node (ref "U3") (pin "23") (pinfunction "PVDD_23") (pintype "power_in"))
      (node (ref "U3") (pin "39") (pinfunction "DVDD_39") (pintype "power_in"))
      (node (ref "U3") (pin "40") (pinfunction "VBAT_40") (pintype "power_in"))
      (node (ref "U3") (pin "5") (pinfunction "TVDD_5") (pintype "power_in"))
      (node (ref "U3") (pin "8") (pinfunction "AVDD_8") (pintype "power_in"))
      (node (ref "U4") (pin "5") (pinfunction "OUT_5") (pintype "passive"))
    )
    (net (code "26") (name "DTR") (class "Default")
      (node (ref "Q6") (pin "2") (pinfunction "E_2") (pintype "passive"))
      (node (ref "R30") (pin "2") (pinfunction "2_2") (pintype "passive"))
      (node (ref "U6") (pin "23") (pinfunction "~{DTR}_23") (pintype "bidirectional"))
    )
    (net (code "27") (name "GND") (class "Default")
      (node (ref "C10") (pin "2") (pinfunction "2_2") (pintype "passive"))
      (node (ref "C11") (pin "1") (pinfunction "1_1") (pintype "passive"))
      (node (ref "C12") (pin "1") (pinfunction "1_1") (pintype "passive"))
      (node (ref "C13") (pin "1") (pinfunction "1_1") (pintype "passive"))
      (node (ref "C14") (pin "1") (pinfunction "1_1") (pintype "passive"))
      (node (ref "C15") (pin "1") (pinfunction "1_1") (pintype "passive"))
      (node (ref "C16") (pin "1") (pinfunction "1_1") (pintype "passive"))
      (node (ref "C18") (pin "2") (pinfunction "2_2") (pintype "passive"))
      (node (ref "C19") (pin "2") (pinfunction "2_2") (pintype "passive"))
      (node (ref "C2") (pin "2") (pinfunction "2_2") (pintype "passive"))
      (node (ref "C20") (pin "2") (pinfunction "2_2") (pintype "passive"))
      (node (ref "C21") (pin "2") (pinfunction "2_2") (pintype "passive"))
      (node (ref "C22") (pin "2") (pinfunction "2_2") (pintype "passive"))
      (node (ref "C24") (pin "2") (pinfunction "2_2") (pintype "passive"))
      (node (ref "C25") (pin "2") (pinfunction "2_2") (pintype "passive"))
      (node (ref "C27") (pin "2") (pinfunction "2_2") (pintype "passive"))
      (node (ref "C28") (pin "1") (pinfunction "1_1") (pintype "passive"))
      (node (ref "C29") (pin "1") (pinfunction "1_1") (pintype "passive"))
      (node (ref "C3") (pin "2") (pinfunction "2_2") (pintype "passive"))
      (node (ref "C30") (pin "1") (pinfunction "1_1") (pintype "passive"))
      (node (ref "C31") (pin "1") (pinfunction "1_1") (pintype "passive"))
      (node (ref "C32") (pin "1") (pinfunction "1_1") (pintype "passive"))
      (node (ref "C34") (pin "1") (pinfunction "1_1") (pintype "passive"))
      (node (ref "C35") (pin "2") (pinfunction "2_2") (pintype "passive"))
      (node (ref "C36") (pin "1") (pinfunction "1_1") (pintype "passive"))
      (node (ref "C38") (pin "1") (pinfunction "1_1") (pintype "passive"))
      (node (ref "C39") (pin "1") (pinfunction "1_1") (pintype "passive"))
      (node (ref "C4") (pin "2") (pinfunction "2_2") (pintype "passive"))
      (node (ref "C40") (pin "1") (pinfunction "1_1") (pintype "passive"))
      (node (ref "C41") (pin "1") (pinfunction "1_1") (pintype "passive"))
      (node (ref "C42") (pin "1") (pinfunction "1_1") (pintype "passive"))
      (node (ref "C43") (pin "1") (pinfunction "1_1") (pintype "passive"))
      (node (ref "C44") (pin "1") (pinfunction "1_1") (pintype "passive"))
      (node (ref "C5") (pin "2") (pinfunction "2_2") (pintype "passive"))
      (node (ref "C6") (pin "2") (pinfunction "2_2") (pintype "passive"))
      (node (ref "C7") (pin "2") (pinfunction "2_2") (pintype "passive"))
      (node (ref "C8") (pin "2") (pinfunction "2_2") (pintype "passive"))
      (node (ref "C9") (pin "2") (pinfunction "2_2") (pintype "passive"))
      (node (ref "D1") (pin "-") (pinfunction "-_-") (pintype "passive"))
      (node (ref "E2") (pin "GND@1") (pinfunction "GND_GND@1") (pintype "bidirectional"))
      (node (ref "E2") (pin "GND@2") (pinfunction "GND_GND@2") (pintype "bidirectional"))
      (node (ref "E2") (pin "GND@3") (pinfunction "GND_GND@3") (pintype "bidirectional"))
      (node (ref "J1") (pin "1") (pinfunction "2_1") (pintype "passive"))
      (node (ref "J3") (pin "5") (pinfunction "GND_5") (pintype "bidirectional"))
      (node (ref "J3") (pin "P1") (pinfunction "GND_P1") (pintype "bidirectional"))
      (node (ref "J3") (pin "P3") (pinfunction "GND_P3") (pintype "bidirectional"))
      (node (ref "J3") (pin "P4") (pinfunction "GND_P4") (pintype "bidirectional"))
      (node (ref "J3") (pin "P5") (pinfunction "GND_P5") (pintype "bidirectional"))
      (node (ref "J3") (pin "P6") (pinfunction "GND_P6") (pintype "bidirectional"))
      (node (ref "J4") (pin "8") (pinfunction "8_8") (pintype "bidirectional"))
      (node (ref "J4") (pin "P1") (pinfunction "P1_P1") (pintype "bidirectional"))
      (node (ref "J4") (pin "P2") (pinfunction "P2_P2") (pintype "bidirectional"))
      (node (ref "PWR") (pin "-") (pinfunction "-_-") (pintype "passive"))
      (node (ref "Q2") (pin "3") (pinfunction "D_3") (pintype "passive"))
      (node (ref "Q3") (pin "2") (pinfunction "S_2") (pintype "passive"))
      (node (ref "R10") (pin "1") (pinfunction "1_1") (pintype "passive"))
      (node (ref "R16") (pin "2") (pinfunction "2_2") (pintype "passive"))
      (node (ref "R17") (pin "2") (pinfunction "2_2") (pintype "passive"))
      (node (ref "R20") (pin "1") (pinfunction "1_1") (pintype "passive"))
      (node (ref "R29") (pin "1") (pinfunction "1_1") (pintype "passive"))
      (node (ref "R3") (pin "1") (pinfunction "1_1") (pintype "passive"))
      (node (ref "R49") (pin "2") (pinfunction "2_2") (pintype "passive"))
      (node (ref "R55") (pin "2") (pinfunction "2_2") (pintype "passive"))
      (node (ref "R56") (pin "1") (pinfunction "1_1") (pintype "passive"))
      (node (ref "RST") (pin "B0") (pinfunction "B0_B0") (pintype "bidirectional"))
      (node (ref "RST") (pin "B1") (pinfunction "B1_B1") (pintype "bidirectional"))
      (node (ref "U$1") (pin "17") (pinfunction "GND_17") (pintype "bidirectional"))
      (node (ref "U$1") (pin "EP") (pinfunction "GND_EP") (pintype "bidirectional"))
      (node (ref "U1") (pin "2") (pinfunction "GND_2") (pintype "bidirectional"))
      (node (ref "U2") (pin "19") (pinfunction "GND_19") (pintype "bidirectional"))
      (node (ref "U2") (pin "21") (pinfunction "GND_21") (pintype "bidirectional"))
      (node (ref "U2") (pin "22") (pinfunction "GND_22") (pintype "bidirectional"))
      (node (ref "U2") (pin "35") (pinfunction "GND_35") (pintype "bidirectional"))
      (node (ref "U2") (pin "40") (pinfunction "GND_40") (pintype "bidirectional"))
      (node (ref "U2") (pin "41") (pinfunction "PAD_41") (pintype "bidirectional"))
      (node (ref "U2") (pin "42") (pinfunction "PAD1_42") (pintype "bidirectional"))
      (node (ref "U2") (pin "43") (pinfunction "PAD2_43") (pintype "bidirectional"))
      (node (ref "U2") (pin "44") (pinfunction "PAD3_44") (pintype "bidirectional"))
      (node (ref "U3") (pin "1") (pinfunction "DVSS_1") (pintype "power_in"))
      (node (ref "U3") (pin "11") (pinfunction "AVSS_11") (pintype "power_in"))
      (node (ref "U3") (pin "17") (pinfunction "I1_17") (pintype "input"))
      (node (ref "U3") (pin "18") (pinfunction "TESTEN_18") (pintype "input"))
      (node (ref "U3") (pin "3") (pinfunction "TVSS1_3") (pintype "power_in"))
      (node (ref "U3") (pin "41") (pinfunction "HEAT_41") (pintype "bidirectional"))
      (node (ref "U3") (pin "7") (pinfunction "TVSS2_7") (pintype "power_in"))
      (node (ref "U4") (pin "2") (pinfunction "GND_2") (pintype "input"))
      (node (ref "U6") (pin "2") (pinfunction "GND_2") (pintype "bidirectional"))
      (node (ref "U6") (pin "PAD") (pinfunction "GND_PAD") (pintype "bidirectional"))
      (node (ref "U8") (pin "2") (pinfunction "VSS_2") (pintype "power_in"))
      (node (ref "USR") (pin "-") (pinfunction "-_-") (pintype "passive"))
    )
    (net (code "28") (name "GPIO0") (class "Default")
      (node (ref "R24") (pin "1") (pinfunction "1_1") (pintype "passive"))
      (node (ref "U2") (pin "23") (pinfunction "GPIO0_23") (pintype "bidirectional"))
      (node (ref "U3") (pin "25") (pinfunction "IP70_RQ_25") (pintype "output"))
    )
    (net (code "29") (name "GPIO29") (class "Default")
      (node (ref "R1") (pin "1") (pinfunction "1_1") (pintype "passive"))
      (node (ref "R13") (pin "1") (pinfunction "1_1") (pintype "passive"))
      (node (ref "U2") (pin "1") (pinfunction "GPIO29_1") (pintype "bidirectional"))
    )
    (net (code "30") (name "GPIO30") (class "Default")
      (node (ref "R36") (pin "1") (pinfunction "1_1") (pintype "passive"))
      (node (ref "U2") (pin "2") (pinfunction "GPIO30_2") (pintype "bidirectional"))
    )
    (net (code "31") (name "GPIO31") (class "Default")
      (node (ref "R12") (pin "1") (pinfunction "1_1") (pintype "passive"))
      (node (ref "R37") (pin "1") (pinfunction "1_1") (pintype "passive"))
      (node (ref "U2") (pin "38") (pinfunction "GPIO31_38") (pintype "bidirectional"))
    )
    (net (code "32") (name "GPIO32") (class "Default")
      (node (ref "R11") (pin "1") (pinfunction "1_1") (pintype "passive"))
      (node (ref "U2") (pin "37") (pinfunction "GPIO32_37") (pintype "bidirectional"))
    )
    (net (code "33") (name "GPIO33") (class "Default")
      (node (ref "R5") (pin "1") (pinfunction "1_1") (pintype "passive"))
      (node (ref "U2") (pin "18") (pinfunction "GPIO33_18") (pintype "bidirectional"))
    )
    (net (code "34") (name "GPIO34") (class "Default")
      (node (ref "R4") (pin "1") (pinfunction "1_1") (pintype "passive"))
      (node (ref "U2") (pin "17") (pinfunction "GPIO34_17") (pintype "bidirectional"))
    )
    (net (code "35") (name "GPIO36") (class "Default")
      (node (ref "R6") (pin "1") (pinfunction "1_1") (pintype "passive"))
      (node (ref "U2") (pin "15") (pinfunction "GPIO36_15") (pintype "bidirectional"))
    )
    (net (code "36") (name "GPIO37") (class "Default")
      (node (ref "D") (pin "A1") (pinfunction "A1_A1") (pintype "bidirectional"))
      (node (ref "Q8") (pin "3") (pinfunction "C_3") (pintype "passive"))
      (node (ref "U2") (pin "13") (pinfunction "GPIO37_13") (pintype "bidirectional"))
    )
    (net (code "37") (name "GPIO39") (class "Default")
      (node (ref "R39") (pin "1") (pinfunction "1_1") (pintype "passive"))
      (node (ref "U2") (pin "10") (pinfunction "GPIO39_10") (pintype "bidirectional"))
    )
    (net (code "38") (name "GPIO57") (class "Default")
      (node (ref "R7") (pin "2") (pinfunction "2_2") (pintype "passive"))
      (node (ref "U2") (pin "9") (pinfunction "GPIO57_9") (pintype "bidirectional"))
    )
    (net (code "39") (name "GPIO58") (class "Default")
      (node (ref "R51") (pin "1") (pinfunction "1_1") (pintype "passive"))
      (node (ref "U2") (pin "8") (pinfunction "GPIO58_8") (pintype "bidirectional"))
    )
    (net (code "40") (name "GPIO59") (class "Default")
      (node (ref "R8") (pin "1") (pinfunction "1_1") (pintype "passive"))
      (node (ref "U2") (pin "7") (pinfunction "GPIO59_7") (pintype "bidirectional"))
    )
    (net (code "41") (name "GPIO60") (class "Default")
      (node (ref "R46") (pin "1") (pinfunction "1_1") (pintype "passive"))
      (node (ref "U2") (pin "6") (pinfunction "GPIO60_6") (pintype "bidirectional"))
    )
    (net (code "42") (name "Net-(0-PadA0)") (class "Default")
      (node (ref "0") (pin "A0") (pinfunction "A0_A0") (pintype "bidirectional"))
      (node (ref "9") (pin "A1") (pinfunction "A1_A1") (pintype "bidirectional"))
    )
    (net (code "43") (name "Net-(0-PadB1)") (class "Default")
      (node (ref "0") (pin "B1") (pinfunction "B1_B1") (pintype "bidirectional"))
      (node (ref "DEL") (pin "B0") (pinfunction "B0_B0") (pintype "bidirectional"))
    )
    (net (code "44") (name "Net-(1-PadA0)") (class "Default")
      (node (ref "1") (pin "A0") (pinfunction "A0_A0") (pintype "bidirectional"))
      (node (ref "C") (pin "A1") (pinfunction "A1_A1") (pintype "bidirectional"))
    )
    (net (code "45") (name "Net-(1-PadA1)") (class "Default")
      (node (ref "1") (pin "A1") (pinfunction "A1_A1") (pintype "bidirectional"))
      (node (ref "2") (pin "A0") (pinfunction "A0_A0") (pintype "bidirectional"))
    )
    (net (code "46") (name "Net-(1-PadB0)") (class "Default")
      (node (ref "1") (pin "B0") (pinfunction "B0_B0") (pintype "bidirectional"))
      (node (ref "4") (pin "B1") (pinfunction "B1_B1") (pintype "bidirectional"))
    )
    (net (code "47") (name "Net-(1-PadB1)") (class "Default")
      (node (ref "1") (pin "B1") (pinfunction "B1_B1") (pintype "bidirectional"))
      (node (ref "R22") (pin "2") (pinfunction "2_2") (pintype "passive"))
      (node (ref "R52") (pin "1") (pinfunction "1_1") (pintype "passive"))
    )
    (net (code "48") (name "Net-(2-PadA1)") (class "Default")
      (node (ref "2") (pin "A1") (pinfunction "A1_A1") (pintype "bidirectional"))
      (node (ref "3") (pin "A0") (pinfunction "A0_A0") (pintype "bidirectional"))
    )
    (net (code "49") (name "Net-(2-PadB0)") (class "Default")
      (node (ref "2") (pin "B0") (pinfunction "B0_B0") (pintype "bidirectional"))
      (node (ref "5") (pin "B1") (pinfunction "B1_B1") (pintype "bidirectional"))
    )
    (net (code "50") (name "Net-(2-PadB1)") (class "Default")
      (node (ref "2") (pin "B1") (pinfunction "B1_B1") (pintype "bidirectional"))
      (node (ref "R22") (pin "1") (pinfunction "1_1") (pintype "passive"))
      (node (ref "R40") (pin "2") (pinfunction "2_2") (pintype "passive"))
    )
    (net (code "51") (name "Net-(3-PadA1)") (class "Default")
      (node (ref "3") (pin "A1") (pinfunction "A1_A1") (pintype "bidirectional"))
      (node (ref "ENTER") (pin "A0") (pinfunction "A0_A0") (pintype "bidirectional"))
    )
    (net (code "52") (name "Net-(3-PadB0)") (class "Default")
      (node (ref "3") (pin "B0") (pinfunction "B0_B0") (pintype "bidirectional"))
      (node (ref "6") (pin "B1") (pinfunction "B1_B1") (pintype "bidirectional"))
    )
    (net (code "53") (name "Net-(3-PadB1)") (class "Default")
      (node (ref "3") (pin "B1") (pinfunction "B1_B1") (pintype "bidirectional"))
      (node (ref "R40") (pin "1") (pinfunction "1_1") (pintype "passive"))
      (node (ref "R50") (pin "1") (pinfunction "1_1") (pintype "passive"))
    )
    (net (code "54") (name "Net-(4-PadA0)") (class "Default")
      (node (ref "4") (pin "A0") (pinfunction "A0_A0") (pintype "bidirectional"))
      (node (ref "B") (pin "A1") (pinfunction "A1_A1") (pintype "bidirectional"))
    )
    (net (code "55") (name "Net-(4-PadA1)") (class "Default")
      (node (ref "4") (pin "A1") (pinfunction "A1_A1") (pintype "bidirectional"))
      (node (ref "5") (pin "A0") (pinfunction "A0_A0") (pintype "bidirectional"))
    )
    (net (code "56") (name "Net-(4-PadB0)") (class "Default")
      (node (ref "4") (pin "B0") (pinfunction "B0_B0") (pintype "bidirectional"))
      (node (ref "7") (pin "B1") (pinfunction "B1_B1") (pintype "bidirectional"))
    )
    (net (code "57") (name "Net-(5-PadA1)") (class "Default")
      (node (ref "5") (pin "A1") (pinfunction "A1_A1") (pintype "bidirectional"))
      (node (ref "6") (pin "A0") (pinfunction "A0_A0") (pintype "bidirectional"))
    )
    (net (code "58") (name "Net-(5-PadB0)") (class "Default")
      (node (ref "5") (pin "B0") (pinfunction "B0_B0") (pintype "bidirectional"))
      (node (ref "8") (pin "B1") (pinfunction "B1_B1") (pintype "bidirectional"))
    )
    (net (code "59") (name "Net-(6-PadA1)") (class "Default")
      (node (ref "6") (pin "A1") (pinfunction "A1_A1") (pintype "bidirectional"))
      (node (ref "DEL") (pin "A0") (pinfunction "A0_A0") (pintype "bidirectional"))
    )
    (net (code "60") (name "Net-(6-PadB0)") (class "Default")
      (node (ref "6") (pin "B0") (pinfunction "B0_B0") (pintype "bidirectional"))
      (node (ref "9") (pin "B1") (pinfunction "B1_B1") (pintype "bidirectional"))
    )
    (net (code "61") (name "Net-(7-PadA0)") (class "Default")
      (node (ref "7") (pin "A0") (pinfunction "A0_A0") (pintype "bidirectional"))
      (node (ref "A") (pin "A1") (pinfunction "A1_A1") (pintype "bidirectional"))
    )
    (net (code "62") (name "Net-(7-PadA1)") (class "Default")
      (node (ref "7") (pin "A1") (pinfunction "A1_A1") (pintype "bidirectional"))
      (node (ref "8") (pin "A0") (pinfunction "A0_A0") (pintype "bidirectional"))
    )
    (net (code "63") (name "Net-(8-PadA1)") (class "Default")
      (node (ref "8") (pin "A1") (pinfunction "A1_A1") (pintype "bidirectional"))
      (node (ref "9") (pin "A0") (pinfunction "A0_A0") (pintype "bidirectional"))
    )
    (net (code "64") (name "Net-(A-PadB1)") (class "Default")
      (node (ref "A") (pin "B1") (pinfunction "B1_B1") (pintype "bidirectional"))
      (node (ref "B") (pin "B0") (pinfunction "B0_B0") (pintype "bidirectional"))
    )
    (net (code "65") (name "Net-(B-PadB1)") (class "Default")
      (node (ref "B") (pin "B1") (pinfunction "B1_B1") (pintype "bidirectional"))
      (node (ref "C") (pin "B0") (pinfunction "B0_B0") (pintype "bidirectional"))
    )
    (net (code "66") (name "Net-(C4-Pad1)") (class "Default")
      (node (ref "C4") (pin "1") (pinfunction "1_1") (pintype "passive"))
      (node (ref "J4") (pin "7") (pinfunction "7_7") (pintype "bidirectional"))
    )
    (net (code "67") (name "Net-(C16-Pad2)") (class "Default")
      (node (ref "C16") (pin "2") (pinfunction "2_2") (pintype "passive"))
      (node (ref "C26") (pin "1") (pinfunction "1_1") (pintype "passive"))
      (node (ref "L2") (pin "1") (pinfunction "1_1") (pintype "passive"))
    )
    (net (code "68") (name "Net-(C23-Pad1)") (class "Default")
      (node (ref "C23") (pin "1") (pinfunction "1_1") (pintype "passive"))
      (node (ref "D1") (pin "+") (pinfunction "+_+") (pintype "passive"))
      (node (ref "D2") (pin "-") (pinfunction "-_-") (pintype "passive"))
    )
    (net (code "69") (name "Net-(C25-Pad1)") (class "Default")
      (node (ref "C25") (pin "1") (pinfunction "1_1") (pintype "passive"))
      (node (ref "C33") (pin "1") (pinfunction "1_1") (pintype "passive"))
      (node (ref "L4") (pin "1") (pinfunction "1_1") (pintype "passive"))
      (node (ref "R23") (pin "2") (pinfunction "2_2") (pintype "passive"))
    )
    (net (code "70") (name "Net-(C37-Pad2)") (class "Default")
      (node (ref "C37") (pin "2") (pinfunction "2_2") (pintype "passive"))
      (node (ref "R23") (pin "1") (pinfunction "1_1") (pintype "passive"))
    )
    (net (code "71") (name "Net-(CHARGE-Pad-)") (class "Default")
      (node (ref "CHARGE") (pin "-") (pinfunction "-_-") (pintype "passive"))
      (node (ref "R57") (pin "2") (pinfunction "2_2") (pintype "passive"))
    )
    (net (code "72") (name "Net-(DEL-PadA1)") (class "Default")
      (node (ref "DEL") (pin "A1") (pinfunction "A1_A1") (pintype "bidirectional"))
      (node (ref "R47") (pin "2") (pinfunction "2_2") (pintype "passive"))
      (node (ref "R48") (pin "1") (pinfunction "1_1") (pintype "passive"))
    )
    (net (code "73") (name "Net-(DEL-PadB1)") (class "Default")
      (node (ref "DEL") (pin "B1") (pinfunction "B1_B1") (pintype "bidirectional"))
      (node (ref "ENTER") (pin "B0") (pinfunction "B0_B0") (pintype "bidirectional"))
    )
    (net (code "74") (name "Net-(E2-SIGNAL)") (class "Default")
      (node (ref "C41") (pin "2") (pinfunction "2_2") (pintype "passive"))
      (node (ref "E2") (pin "FEED") (pinfunction "SIGNAL_FEED") (pintype "bidirectional"))
      (node (ref "L7") (pin "1") (pinfunction "1_1") (pintype "passive"))
    )
    (net (code "75") (name "Net-(ENTER-PadA1)") (class "Default")
      (node (ref "ENTER") (pin "A1") (pinfunction "A1_A1") (pintype "bidirectional"))
      (node (ref "R47") (pin "1") (pinfunction "1_1") (pintype "passive"))
    )
    (net (code "76") (name "Net-(ENTER-PadB1)") (class "Default")
      (node (ref "ENTER") (pin "B1") (pinfunction "B1_B1") (pintype "bidirectional"))
      (node (ref "R50") (pin "2") (pinfunction "2_2") (pintype "passive"))
    )
    (net (code "77") (name "Net-(J1-1)") (class "Default")
      (node (ref "C39") (pin "2") (pinfunction "2_2") (pintype "passive"))
      (node (ref "D5") (pin "A") (pinfunction "A_A") (pintype "passive"))
      (node (ref "J1") (pin "2") (pinfunction "1_2") (pintype "passive"))
      (node (ref "U8") (pin "3") (pinfunction "VBAT_3") (pintype "power_in"))
    )
    (net (code "78") (name "Net-(J3-VCC)") (class "Default")
      (node (ref "F1") (pin "2") (pinfunction "2_2") (pintype "passive"))
      (node (ref "J3") (pin "1") (pinfunction "VCC_1") (pintype "bidirectional"))
    )
    (net (code "79") (name "Net-(JP2-Pad1)") (class "Default")
      (node (ref "JP2") (pin "1") (pinfunction "1_1") (pintype "passive"))
      (node (ref "R18") (pin "2") (pinfunction "2_2") (pintype "passive"))
    )
    (net (code "80") (name "Net-(PWR-Pad+)") (class "Default")
      (node (ref "PWR") (pin "+") (pinfunction "+_+") (pintype "passive"))
      (node (ref "R18") (pin "1") (pinfunction "1_1") (pintype "passive"))
    )
    (net (code "81") (name "Net-(Q1-S)") (class "Default")
      (node (ref "Q1") (pin "2") (pinfunction "S_2") (pintype "passive"))
      (node (ref "R42") (pin "1") (pinfunction "1_1") (pintype "passive"))
      (node (ref "U6") (pin "20") (pinfunction "RXD_20") (pintype "bidirectional"))
    )
    (net (code "82") (name "Net-(Q2-S)") (class "Default")
      (node (ref "Q2") (pin "2") (pinfunction "S_2") (pintype "passive"))
      (node (ref "U$4") (pin "P$3") (pinfunction "2-_P$3") (pintype "bidirectional"))
    )
    (net (code "83") (name "Net-(Q3-D)") (class "Default")
      (node (ref "Q3") (pin "3") (pinfunction "D_3") (pintype "passive"))
      (node (ref "R15") (pin "1") (pinfunction "1_1") (pintype "passive"))
      (node (ref "U1") (pin "3") (pinfunction "EN_3") (pintype "bidirectional"))
    )
    (net (code "84") (name "Net-(Q5-B)") (class "Default")
      (node (ref "Q5") (pin "1") (pinfunction "B_1") (pintype "passive"))
      (node (ref "R30") (pin "1") (pinfunction "1_1") (pintype "passive"))
    )
    (net (code "85") (name "Net-(Q6-B)") (class "Default")
      (node (ref "Q6") (pin "1") (pinfunction "B_1") (pintype "passive"))
      (node (ref "R27") (pin "2") (pinfunction "2_2") (pintype "passive"))
    )
    (net (code "86") (name "Net-(Q6-C)") (class "Default")
      (node (ref "Q6") (pin "3") (pinfunction "C_3") (pintype "passive"))
      (node (ref "R19") (pin "2") (pinfunction "2_2") (pintype "passive"))
      (node (ref "R25") (pin "2") (pinfunction "2_2") (pintype "passive"))
    )
    (net (code "87") (name "Net-(Q7-S)") (class "Default")
      (node (ref "Q7") (pin "2") (pinfunction "S_2") (pintype "passive"))
      (node (ref "R43") (pin "1") (pinfunction "1_1") (pintype "passive"))
      (node (ref "U6") (pin "21") (pinfunction "TXD_21") (pintype "bidirectional"))
    )
    (net (code "88") (name "Net-(Q8-B)") (class "Default")
      (node (ref "Q8") (pin "1") (pinfunction "B_1") (pintype "passive"))
      (node (ref "R25") (pin "1") (pinfunction "1_1") (pintype "passive"))
    )
    (net (code "89") (name "Net-(Q9-D)") (class "Default")
      (node (ref "C23") (pin "2") (pinfunction "2_2") (pintype "passive"))
      (node (ref "D3") (pin "+") (pinfunction "+_+") (pintype "passive"))
      (node (ref "L1") (pin "2") (pinfunction "2_2") (pintype "passive"))
      (node (ref "Q9") (pin "3") (pinfunction "D_3") (pintype "passive"))
    )
    (net (code "90") (name "Net-(R7-Pad1)") (class "Default")
      (node (ref "R7") (pin "1") (pinfunction "1_1") (pintype "passive"))
      (node (ref "USR") (pin "+") (pinfunction "+_+") (pintype "passive"))
    )
    (net (code "91") (name "Net-(R14-Pad1)") (class "Default")
      (node (ref "R14") (pin "1") (pinfunction "1_1") (pintype "passive"))
      (node (ref "R2") (pin "1") (pinfunction "1_1") (pintype "passive"))
      (node (ref "R55") (pin "1") (pinfunction "1_1") (pintype "passive"))
    )
    (net (code "92") (name "Net-(R34-Pad1)") (class "Default")
      (node (ref "R34") (pin "1") (pinfunction "1_1") (pintype "passive"))
      (node (ref "RX") (pin "+") (pinfunction "+_+") (pintype "passive"))
    )
    (net (code "93") (name "Net-(R35-Pad1)") (class "Default")
      (node (ref "R35") (pin "1") (pinfunction "1_1") (pintype "passive"))
      (node (ref "TX") (pin "+") (pinfunction "+_+") (pintype "passive"))
    )
    (net (code "94") (name "Net-(SW2-B)") (class "Default")
      (node (ref "SW2") (pin "3") (pinfunction "B_3") (pintype "bidirectional"))
      (node (ref "U$4") (pin "P$1") (pinfunction "1-_P$1") (pintype "bidirectional"))
    )
    (net (code "95") (name "Net-(SW2-COM)") (class "Default")
      (node (ref "SW2") (pin "2") (pinfunction "COM_2") (pintype "bidirectional"))
      (node (ref "U$4") (pin "P$2") (pinfunction "2+_P$2") (pintype "bidirectional"))
    )
    (net (code "96") (name "Net-(U$1-MISO)") (class "Default")
      (node (ref "R36") (pin "2") (pinfunction "2_2") (pintype "passive"))
      (node (ref "U$1") (pin "11") (pinfunction "MISO_11") (pintype "bidirectional"))
    )
    (net (code "97") (name "Net-(U$1-MOSI)") (class "Default")
      (node (ref "R1") (pin "2") (pinfunction "2_2") (pintype "passive"))
      (node (ref "U$1") (pin "10") (pinfunction "MOSI_10") (pintype "bidirectional"))
    )
    (net (code "98") (name "Net-(U$1-SCK)") (class "Default")
      (node (ref "R37") (pin "2") (pinfunction "2_2") (pintype "passive"))
      (node (ref "U$1") (pin "12") (pinfunction "SCK_12") (pintype "bidirectional"))
    )
    (net (code "99") (name "Net-(U$1-{slash}CS)") (class "Default")
      (node (ref "R39") (pin "2") (pinfunction "2_2") (pintype "passive"))
      (node (ref "R53") (pin "2") (pinfunction "2_2") (pintype "passive"))
      (node (ref "U$1") (pin "13") (pinfunction "/CS_13") (pintype "bidirectional"))
    )
    (net (code "100") (name "Net-(U1-FB)") (class "Default")
      (node (ref "R10") (pin "2") (pinfunction "2_2") (pintype "passive"))
      (node (ref "R9") (pin "1") (pinfunction "1_1") (pintype "passive"))
      (node (ref "U1") (pin "4") (pinfunction "FB_4") (pintype "bidirectional"))
    )
    (net (code "101") (name "Net-(U1-SW)") (class "Default")
      (node (ref "L3") (pin "2") (pinfunction "2_2") (pintype "passive"))
      (node (ref "U1") (pin "1") (pinfunction "SW_1") (pintype "bidirectional"))
    )
    (net (code "102") (name "Net-(U2-NC)") (class "Default")
      (node (ref "C42") (pin "2") (pinfunction "2_2") (pintype "passive"))
      (node (ref "L7") (pin "2") (pinfunction "2_2") (pintype "passive"))
      (node (ref "U2") (pin "20") (pinfunction "NC_20") (pintype "bidirectional"))
    )
    (net (code "103") (name "Net-(U3-OSCIN)") (class "Default")
      (node (ref "C11") (pin "2") (pinfunction "2_2") (pintype "passive"))
      (node (ref "U3") (pin "14") (pinfunction "OSCIN_14") (pintype "input"))
      (node (ref "Y1") (pin "2") (pinfunction "1_2") (pintype "passive"))
    )
    (net (code "104") (name "Net-(U3-OSCOUT)") (class "Default")
      (node (ref "C15") (pin "2") (pinfunction "2_2") (pintype "passive"))
      (node (ref "U3") (pin "15") (pinfunction "OSCOUT_15") (pintype "output"))
      (node (ref "Y1") (pin "4") (pinfunction "2_4") (pintype "passive"))
    )
    (net (code "105") (name "Net-(U3-RX)") (class "Default")
      (node (ref "C37") (pin "1") (pinfunction "1_1") (pintype "passive"))
      (node (ref "R21") (pin "1") (pinfunction "1_1") (pintype "passive"))
      (node (ref "U3") (pin "10") (pinfunction "RX_10") (pintype "input"))
    )
    (net (code "106") (name "Net-(U3-TX1)") (class "Default")
      (node (ref "L2") (pin "2") (pinfunction "2_2") (pintype "passive"))
      (node (ref "U3") (pin "4") (pinfunction "TX1_4") (pintype "output"))
    )
    (net (code "107") (name "Net-(U3-TX2)") (class "Default")
      (node (ref "L4") (pin "2") (pinfunction "2_2") (pintype "passive"))
      (node (ref "U3") (pin "6") (pinfunction "TX2_6") (pintype "output"))
    )
    (net (code "108") (name "Net-(U3-VMID)") (class "Default")
      (node (ref "C36") (pin "2") (pinfunction "2_2") (pintype "passive"))
      (node (ref "R21") (pin "2") (pinfunction "2_2") (pintype "passive"))
      (node (ref "U3") (pin "9") (pinfunction "VMID_9") (pintype "output"))
    )
    (net (code "109") (name "Net-(U4-EN)") (class "Default")
      (node (ref "C9") (pin "1") (pinfunction "1_1") (pintype "passive"))
      (node (ref "D6") (pin "C") (pinfunction "C_C") (pintype "passive"))
      (node (ref "U4") (pin "1") (pinfunction "IN_1") (pintype "input"))
      (node (ref "U4") (pin "3") (pinfunction "EN_3") (pintype "input"))
    )
    (net (code "110") (name "Net-(U6-RXLED{slash}IO1)") (class "Default")
      (node (ref "TX") (pin "-") (pinfunction "-_-") (pintype "passive"))
      (node (ref "U6") (pin "13") (pinfunction "RXLED/IO1_13") (pintype "bidirectional"))
    )
    (net (code "111") (name "Net-(U6-TXLED{slash}IO0)") (class "Default")
      (node (ref "RX") (pin "-") (pinfunction "-_-") (pintype "passive"))
      (node (ref "U6") (pin "14") (pinfunction "TXLED/IO0_14") (pintype "bidirectional"))
    )
    (net (code "112") (name "Net-(U6-~{RESET})") (class "Default")
      (node (ref "R38") (pin "1") (pinfunction "1_1") (pintype "passive"))
      (node (ref "U6") (pin "9") (pinfunction "~{RESET}_9") (pintype "bidirectional"))
    )
    (net (code "113") (name "Net-(U8-PROG)") (class "Default")
      (node (ref "R56") (pin "2") (pinfunction "2_2") (pintype "passive"))
      (node (ref "U8") (pin "5") (pinfunction "PROG_5") (pintype "input"))
    )
    (net (code "114") (name "Net-(U8-STAT)") (class "Default")
      (node (ref "R57") (pin "1") (pinfunction "1_1") (pintype "passive"))
      (node (ref "U8") (pin "1") (pinfunction "STAT_1") (pintype "output"))
    )
    (net (code "115") (name "PMU_EN_WF") (class "Default")
      (node (ref "R31") (pin "2") (pinfunction "2_2") (pintype "passive"))
      (node (ref "U2") (pin "5") (pinfunction "PMU_EN_WF_5") (pintype "bidirectional"))
    )
    (net (code "116") (name "RTS") (class "Default")
      (node (ref "Q5") (pin "2") (pinfunction "E_2") (pintype "passive"))
      (node (ref "R27") (pin "1") (pinfunction "1_1") (pintype "passive"))
      (node (ref "U6") (pin "19") (pinfunction "~{RTS}_19") (pintype "bidirectional"))
    )
    (net (code "117") (name "SCL") (class "Default")
      (node (ref "R33") (pin "2") (pinfunction "2_2") (pintype "passive"))
      (node (ref "U2") (pin "4") (pinfunction "GPIO27_4") (pintype "bidirectional"))
      (node (ref "U3") (pin "27") (pinfunction "NSS/P50_SCL/HSU_RX_27") (pintype "bidirectional"))
    )
    (net (code "118") (name "SDA") (class "Default")
      (node (ref "R32") (pin "2") (pinfunction "2_2") (pintype "passive"))
      (node (ref "U2") (pin "3") (pinfunction "GPIO28_3") (pintype "bidirectional"))
      (node (ref "U3") (pin "28") (pinfunction "MOSI/SDA/HSU_TX_28") (pintype "bidirectional"))
    )
    (net (code "119") (name "SYS_RST_N") (class "Default")
      (node (ref "C27") (pin "1") (pinfunction "1_1") (pintype "passive"))
      (node (ref "Q5") (pin "3") (pinfunction "C_3") (pintype "passive"))
      (node (ref "R41") (pin "2") (pinfunction "2_2") (pintype "passive"))
      (node (ref "RST") (pin "A0") (pinfunction "A0_A0") (pintype "bidirectional"))
      (node (ref "RST") (pin "A1") (pinfunction "A1_A1") (pintype "bidirectional"))
      (node (ref "U2") (pin "11") (pinfunction "SYS_RST_N_11") (pintype "bidirectional"))
    )
    (net (code "120") (name "UART_RX") (class "Default")
      (node (ref "Q7") (pin "3") (pinfunction "D_3") (pintype "passive"))
      (node (ref "R44") (pin "1") (pinfunction "1_1") (pintype "passive"))
      (node (ref "U2") (pin "25") (pinfunction "GPIO2_25") (pintype "bidirectional"))
    )
    (net (code "121") (name "UART_TX") (class "Default")
      (node (ref "Q1") (pin "3") (pinfunction "D_3") (pintype "passive"))
      (node (ref "R45") (pin "1") (pinfunction "1_1") (pintype "passive"))
      (node (ref "U2") (pin "26") (pinfunction "GPIO3_26") (pintype "bidirectional"))
    )
    (net (code "122") (name "USB_D+") (class "Default")
      (node (ref "J3") (pin "3") (pinfunction "DP_3") (pintype "bidirectional"))
      (node (ref "U6") (pin "3") (pinfunction "D+_3") (pintype "bidirectional"))
    )
    (net (code "123") (name "USB_D-") (class "Default")
      (node (ref "J3") (pin "2") (pinfunction "DM_2") (pintype "bidirectional"))
      (node (ref "U6") (pin "4") (pinfunction "D-_4") (pintype "bidirectional"))
    )
    (net (code "124") (name "VCC") (class "Default")
      (node (ref "C30") (pin "2") (pinfunction "2_2") (pintype "passive"))
      (node (ref "Q1") (pin "1") (pinfunction "G_1") (pintype "passive"))
      (node (ref "Q7") (pin "1") (pinfunction "G_1") (pintype "passive"))
      (node (ref "R34") (pin "2") (pinfunction "2_2") (pintype "passive"))
      (node (ref "R35") (pin "2") (pinfunction "2_2") (pintype "passive"))
      (node (ref "R38") (pin "2") (pinfunction "2_2") (pintype "passive"))
      (node (ref "R42") (pin "2") (pinfunction "2_2") (pintype "passive"))
      (node (ref "R43") (pin "2") (pinfunction "2_2") (pintype "passive"))
      (node (ref "U6") (pin "5") (pinfunction "VIO_5") (pintype "bidirectional"))
      (node (ref "U6") (pin "6") (pinfunction "VDD_6") (pintype "bidirectional"))
    )
    (net (code "125") (name "V_BATT") (class "Default")
      (node (ref "C2") (pin "1") (pinfunction "1_1") (pintype "passive"))
      (node (ref "L3") (pin "1") (pinfunction "1_1") (pintype "passive"))
      (node (ref "Q2") (pin "1") (pinfunction "G_1") (pintype "passive"))
      (node (ref "R15") (pin "2") (pinfunction "2_2") (pintype "passive"))
      (node (ref "R28") (pin "2") (pinfunction "2_2") (pintype "passive"))
      (node (ref "TP7") (pin "P$1") (pinfunction "1_P$1") (pintype "bidirectional"))
      (node (ref "U$4") (pin "P$4") (pinfunction "1+_P$4") (pintype "bidirectional"))
      (node (ref "U1") (pin "6") (pinfunction "VIN_6") (pintype "bidirectional"))
    )
    (net (code "126") (name "V_USB") (class "Default")
      (node (ref "C31") (pin "2") (pinfunction "2_2") (pintype "passive"))
      (node (ref "C32") (pin "2") (pinfunction "2_2") (pintype "passive"))
      (node (ref "C44") (pin "2") (pinfunction "2_2") (pintype "passive"))
      (node (ref "CHARGE") (pin "+") (pinfunction "+_+") (pintype "passive"))
      (node (ref "D5") (pin "C") (pinfunction "C_C") (pintype "passive"))
      (node (ref "D6") (pin "A") (pinfunction "A_A") (pintype "passive"))
      (node (ref "F1") (pin "1") (pinfunction "1_1") (pintype "passive"))
      (node (ref "Q3") (pin "1") (pinfunction "G_1") (pintype "passive"))
      (node (ref "R20") (pin "2") (pinfunction "2_2") (pintype "passive"))
      (node (ref "TP6") (pin "P$1") (pinfunction "1_P$1") (pintype "bidirectional"))
      (node (ref "U6") (pin "7") (pinfunction "VREGIN_7") (pintype "bidirectional"))
      (node (ref "U6") (pin "8") (pinfunction "VBUS_8") (pintype "bidirectional"))
      (node (ref "U8") (pin "4") (pinfunction "VIN_4") (pintype "power_in"))
    )
    (net (code "127") (name "unconnected-(0-PadB0)") (class "Default")
      (node (ref "0") (pin "B0") (pinfunction "B0_B0") (pintype "bidirectional"))
    )
    (net (code "128") (name "unconnected-(7-PadB0)") (class "Default")
      (node (ref "7") (pin "B0") (pinfunction "B0_B0") (pintype "bidirectional"))
    )
    (net (code "129") (name "unconnected-(8-PadB0)") (class "Default")
      (node (ref "8") (pin "B0") (pinfunction "B0_B0") (pintype "bidirectional"))
    )
    (net (code "130") (name "unconnected-(9-PadB0)") (class "Default")
      (node (ref "9") (pin "B0") (pinfunction "B0_B0") (pintype "bidirectional"))
    )
    (net (code "131") (name "unconnected-(A-PadA0)") (class "Default")
      (node (ref "A") (pin "A0") (pinfunction "A0_A0") (pintype "bidirectional"))
    )
    (net (code "132") (name "unconnected-(A-PadB0)") (class "Default")
      (node (ref "A") (pin "B0") (pinfunction "B0_B0") (pintype "bidirectional"))
    )
    (net (code "133") (name "unconnected-(B-PadA0)") (class "Default")
      (node (ref "B") (pin "A0") (pinfunction "A0_A0") (pintype "bidirectional"))
    )
    (net (code "134") (name "unconnected-(C-PadA0)") (class "Default")
      (node (ref "C") (pin "A0") (pinfunction "A0_A0") (pintype "bidirectional"))
    )
    (net (code "135") (name "unconnected-(D-PadA0)") (class "Default")
      (node (ref "D") (pin "A0") (pinfunction "A0_A0") (pintype "bidirectional"))
    )
    (net (code "136") (name "unconnected-(D-PadB0)") (class "Default")
      (node (ref "D") (pin "B0") (pinfunction "B0_B0") (pintype "bidirectional"))
    )
    (net (code "137") (name "unconnected-(J3-ID-Pad4)") (class "Default")
      (node (ref "J3") (pin "4") (pinfunction "ID_4") (pintype "bidirectional"))
    )
    (net (code "138") (name "unconnected-(J4-Pad18)") (class "Default")
      (node (ref "J4") (pin "18") (pinfunction "18_18") (pintype "bidirectional"))
    )
    (net (code "139") (name "unconnected-(J4-Pad19)") (class "Default")
      (node (ref "J4") (pin "19") (pinfunction "19_19") (pintype "bidirectional"))
    )
    (net (code "140") (name "unconnected-(SW2-A-Pad1)") (class "Default")
      (node (ref "SW2") (pin "1") (pinfunction "A_1") (pintype "bidirectional"))
    )
    (net (code "141") (name "unconnected-(U$1-D+-Pad5)") (class "Default")
      (node (ref "U$1") (pin "5") (pinfunction "D+_5") (pintype "bidirectional"))
    )
    (net (code "142") (name "unconnected-(U$1-D--Pad20)") (class "Default")
      (node (ref "U$1") (pin "20") (pinfunction "D-_20") (pintype "bidirectional"))
    )
    (net (code "143") (name "unconnected-(U$1-ISO7816_CLK-Pad6)") (class "Default")
      (node (ref "U$1") (pin "6") (pinfunction "ISO7816_CLK_6") (pintype "bidirectional"))
    )
    (net (code "144") (name "unconnected-(U$1-ISO7816_IO-Pad19)") (class "Default")
      (node (ref "U$1") (pin "19") (pinfunction "ISO7816_IO_19") (pintype "bidirectional"))
    )
    (net (code "145") (name "unconnected-(U$1-ISO7816_RST-Pad7)") (class "Default")
      (node (ref "U$1") (pin "7") (pinfunction "ISO7816_RST_7") (pintype "bidirectional"))
    )
    (net (code "146") (name "unconnected-(U2-GPIO1-Pad24)") (class "Default")
      (node (ref "U2") (pin "24") (pinfunction "GPIO1_24") (pintype "bidirectional"))
    )
    (net (code "147") (name "unconnected-(U2-GPIO4-Pad33)") (class "Default")
      (node (ref "U2") (pin "33") (pinfunction "GPIO4_33") (pintype "bidirectional"))
    )
    (net (code "148") (name "unconnected-(U2-GPIO5-Pad29)") (class "Default")
      (node (ref "U2") (pin "29") (pinfunction "GPIO5_29") (pintype "bidirectional"))
    )
    (net (code "149") (name "unconnected-(U2-GPIO6-Pad27)") (class "Default")
      (node (ref "U2") (pin "27") (pinfunction "GPIO6_27") (pintype "bidirectional"))
    )
    (net (code "150") (name "unconnected-(U2-GPIO7-Pad28)") (class "Default")
      (node (ref "U2") (pin "28") (pinfunction "GPIO7_28") (pintype "bidirectional"))
    )
    (net (code "151") (name "unconnected-(U2-GPIO24-Pad30)") (class "Default")
      (node (ref "U2") (pin "30") (pinfunction "GPIO24_30") (pintype "bidirectional"))
    )
    (net (code "152") (name "unconnected-(U2-GPIO25-Pad31)") (class "Default")
      (node (ref "U2") (pin "31") (pinfunction "GPIO25_31") (pintype "bidirectional"))
    )
    (net (code "153") (name "unconnected-(U2-GPIO26-Pad32)") (class "Default")
      (node (ref "U2") (pin "32") (pinfunction "GPIO26_32") (pintype "bidirectional"))
    )
    (net (code "154") (name "unconnected-(U2-GPIO35-Pad16)") (class "Default")
      (node (ref "U2") (pin "16") (pinfunction "GPIO35_16") (pintype "bidirectional"))
    )
    (net (code "155") (name "unconnected-(U2-GPIO38-Pad12)") (class "Default")
      (node (ref "U2") (pin "12") (pinfunction "GPIO38_12") (pintype "bidirectional"))
    )
    (net (code "156") (name "unconnected-(U2-PMU_EN_RTC-Pad36)") (class "Default")
      (node (ref "U2") (pin "36") (pinfunction "PMU_EN_RTC_36") (pintype "bidirectional"))
    )
    (net (code "157") (name "unconnected-(U3-AUX1-Pad12)") (class "Default")
      (node (ref "U3") (pin "12") (pinfunction "AUX1_12") (pintype "output"))
    )
    (net (code "158") (name "unconnected-(U3-AUX2-Pad13)") (class "Default")
      (node (ref "U3") (pin "13") (pinfunction "AUX2_13") (pintype "output"))
    )
    (net (code "159") (name "unconnected-(U3-LOADMOD-Pad2)") (class "Default")
      (node (ref "U3") (pin "2") (pinfunction "LOADMOD_2") (pintype "output"))
    )
    (net (code "160") (name "unconnected-(U3-MISO{slash}P71-Pad29)") (class "Default")
      (node (ref "U3") (pin "29") (pinfunction "MISO/P71_29") (pintype "bidirectional"))
    )
    (net (code "161") (name "unconnected-(U3-NC-Pad20)") (class "Default")
      (node (ref "U3") (pin "20") (pinfunction "NC_20") (pintype "no_connect"))
    )
    (net (code "162") (name "unconnected-(U3-NC1-Pad21)") (class "Default")
      (node (ref "U3") (pin "21") (pinfunction "NC1_21") (pintype "no_connect"))
    )
    (net (code "163") (name "unconnected-(U3-NC2-Pad22)") (class "Default")
      (node (ref "U3") (pin "22") (pinfunction "NC2_22") (pintype "no_connect"))
    )
    (net (code "164") (name "unconnected-(U3-P30{slash}UART_RX-Pad24)") (class "Default")
      (node (ref "U3") (pin "24") (pinfunction "P30/UART_RX_24") (pintype "bidirectional"))
    )
    (net (code "165") (name "unconnected-(U3-P31{slash}UART_TX-Pad31)") (class "Default")
      (node (ref "U3") (pin "31") (pinfunction "P31/UART_TX_31") (pintype "bidirectional"))
    )
    (net (code "166") (name "unconnected-(U3-P32_INT0-Pad32)") (class "Default")
      (node (ref "U3") (pin "32") (pinfunction "P32_INT0_32") (pintype "bidirectional"))
    )
    (net (code "167") (name "unconnected-(U3-P33_INT1-Pad33)") (class "Default")
      (node (ref "U3") (pin "33") (pinfunction "P33_INT1_33") (pintype "bidirectional"))
    )
    (net (code "168") (name "unconnected-(U3-P34{slash}SIC_CLK-Pad34)") (class "Default")
      (node (ref "U3") (pin "34") (pinfunction "P34/SIC_CLK_34") (pintype "bidirectional"))
    )
    (net (code "169") (name "unconnected-(U3-P35-Pad19)") (class "Default")
      (node (ref "U3") (pin "19") (pinfunction "P35_19") (pintype "bidirectional"))
    )
    (net (code "170") (name "unconnected-(U3-RSTOUT_N-Pad26)") (class "Default")
      (node (ref "U3") (pin "26") (pinfunction "RSTOUT_N_26") (pintype "bidirectional"))
    )
    (net (code "171") (name "unconnected-(U3-SCK{slash}P72-Pad30)") (class "Default")
      (node (ref "U3") (pin "30") (pinfunction "SCK/P72_30") (pintype "bidirectional"))
    )
    (net (code "172") (name "unconnected-(U3-SIGIN-Pad36)") (class "Default")
      (node (ref "U3") (pin "36") (pinfunction "SIGIN_36") (pintype "input"))
    )
    (net (code "173") (name "unconnected-(U3-SIGOUT-Pad35)") (class "Default")
      (node (ref "U3") (pin "35") (pinfunction "SIGOUT_35") (pintype "output"))
    )
    (net (code "174") (name "unconnected-(U4-BP-Pad4)") (class "Default")
      (node (ref "U4") (pin "4") (pinfunction "BP_4") (pintype "input"))
    )
    (net (code "175") (name "unconnected-(U6-RS485{slash}IO2-Pad12)") (class "Default")
      (node (ref "U6") (pin "12") (pinfunction "RS485/IO2_12") (pintype "bidirectional"))
    )
    (net (code "176") (name "unconnected-(U6-SUSPEND-Pad17)") (class "Default")
      (node (ref "U6") (pin "17") (pinfunction "SUSPEND_17") (pintype "bidirectional"))
    )
    (net (code "177") (name "unconnected-(U6-WAKEUP{slash}IO3-Pad11)") (class "Default")
      (node (ref "U6") (pin "11") (pinfunction "WAKEUP/IO3_11") (pintype "bidirectional"))
    )
    (net (code "178") (name "unconnected-(U6-~{CTS}-Pad18)") (class "Default")
      (node (ref "U6") (pin "18") (pinfunction "~{CTS}_18") (pintype "bidirectional"))
    )
    (net (code "179") (name "unconnected-(U6-~{DCD}-Pad24)") (class "Default")
      (node (ref "U6") (pin "24") (pinfunction "~{DCD}_24") (pintype "bidirectional"))
    )
    (net (code "180") (name "unconnected-(U6-~{DSR}-Pad22)") (class "Default")
      (node (ref "U6") (pin "22") (pinfunction "~{DSR}_22") (pintype "bidirectional"))
    )
    (net (code "181") (name "unconnected-(U6-~{RI}{slash}CLK-Pad1)") (class "Default")
      (node (ref "U6") (pin "1") (pinfunction "~{RI}/CLK_1") (pintype "bidirectional"))
    )
    (net (code "182") (name "unconnected-(U6-~{SUSPEND}-Pad15)") (class "Default")
      (node (ref "U6") (pin "15") (pinfunction "~{SUSPEND}_15") (pintype "bidirectional"))
    )
  )
)
